# BITalino_V3.net
KiCad netlist of a schematic drawn in EAGLE
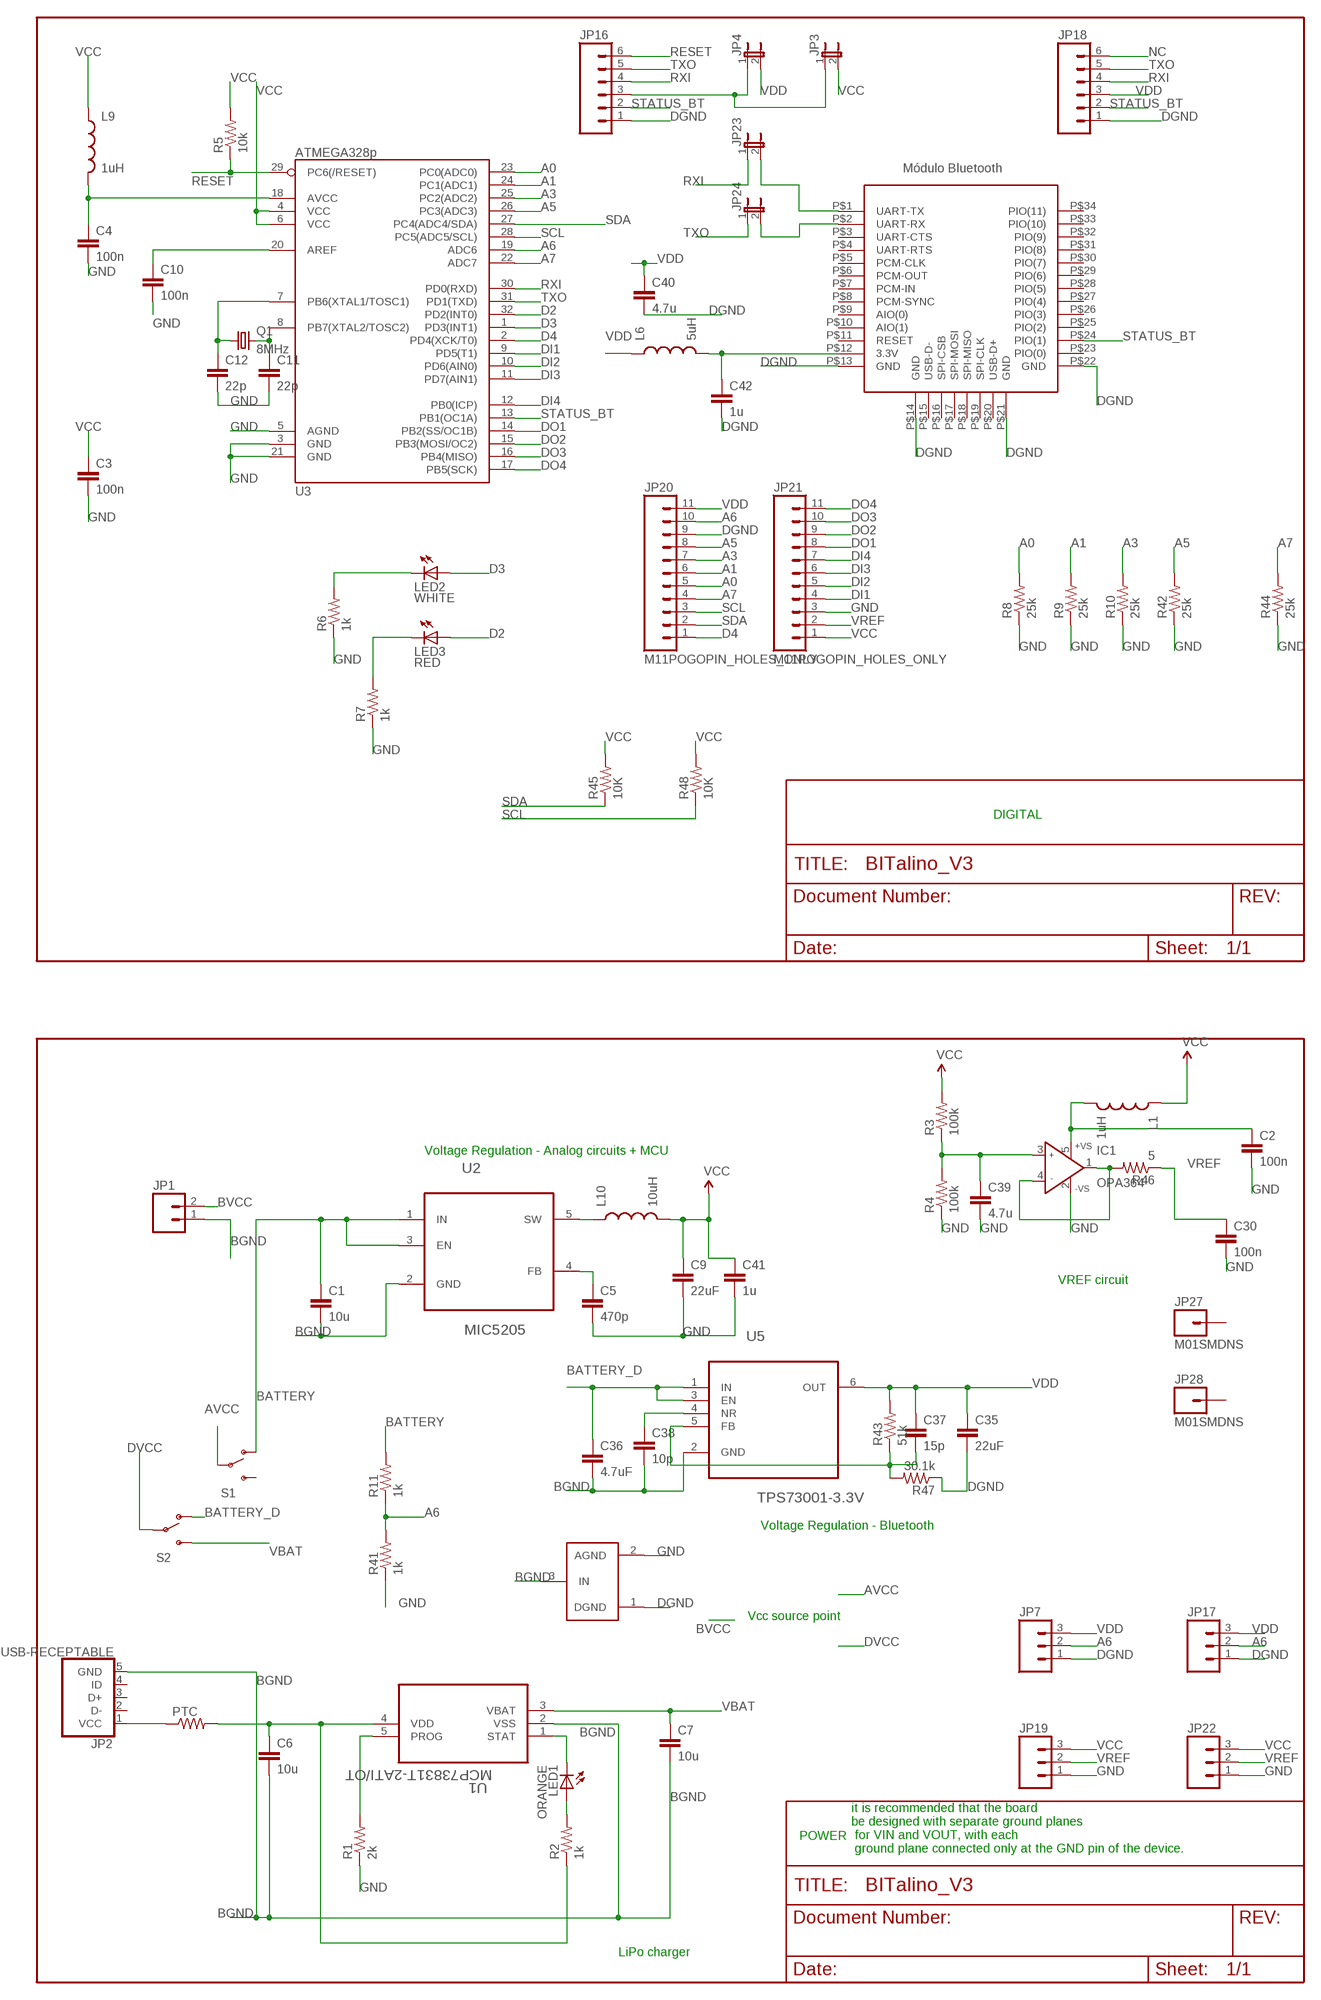
[diagram p0: schematic, sheet 1, part 1 of 3]
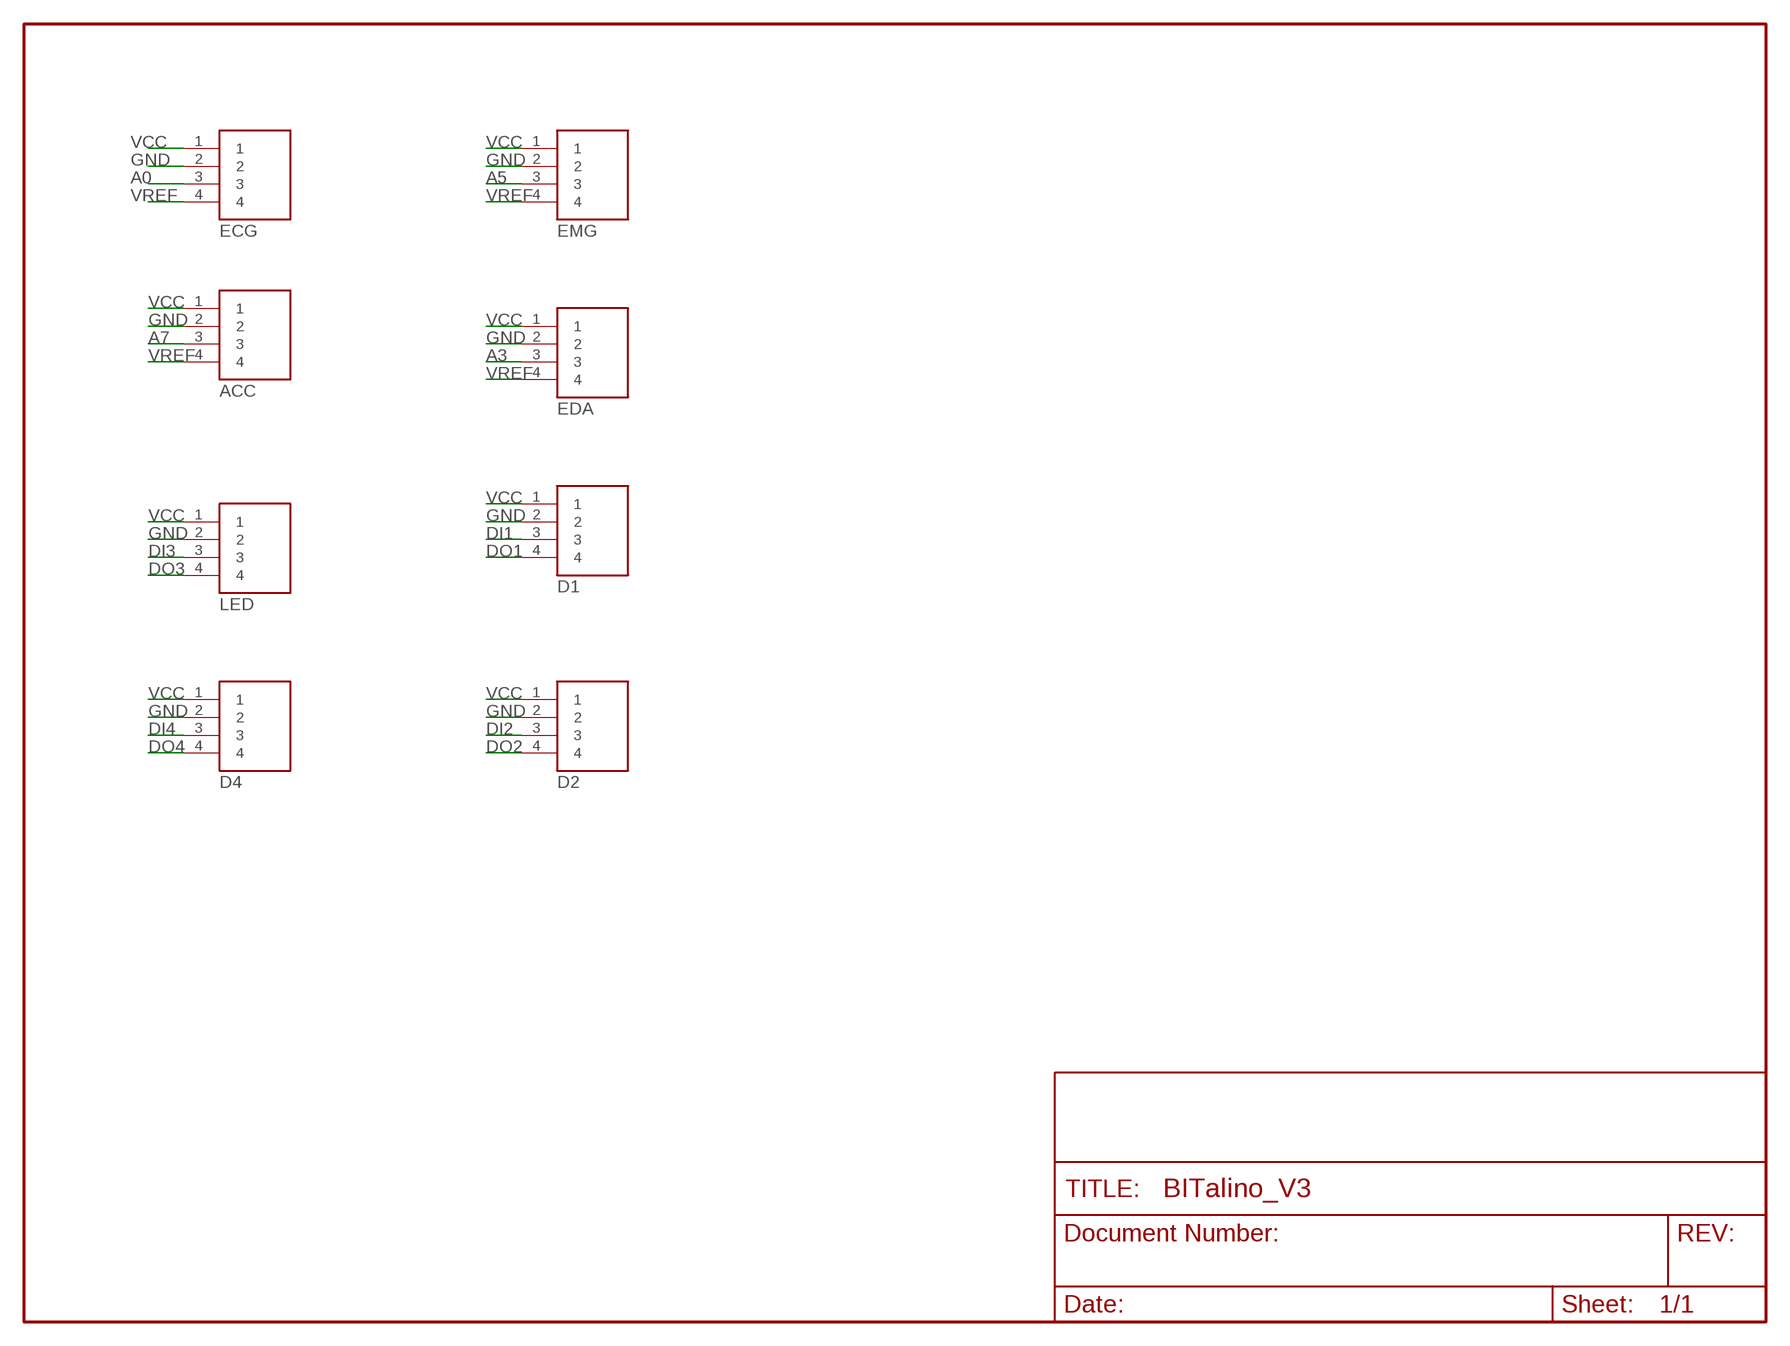
[diagram p1: schematic, sheet 1, part 2 of 3]
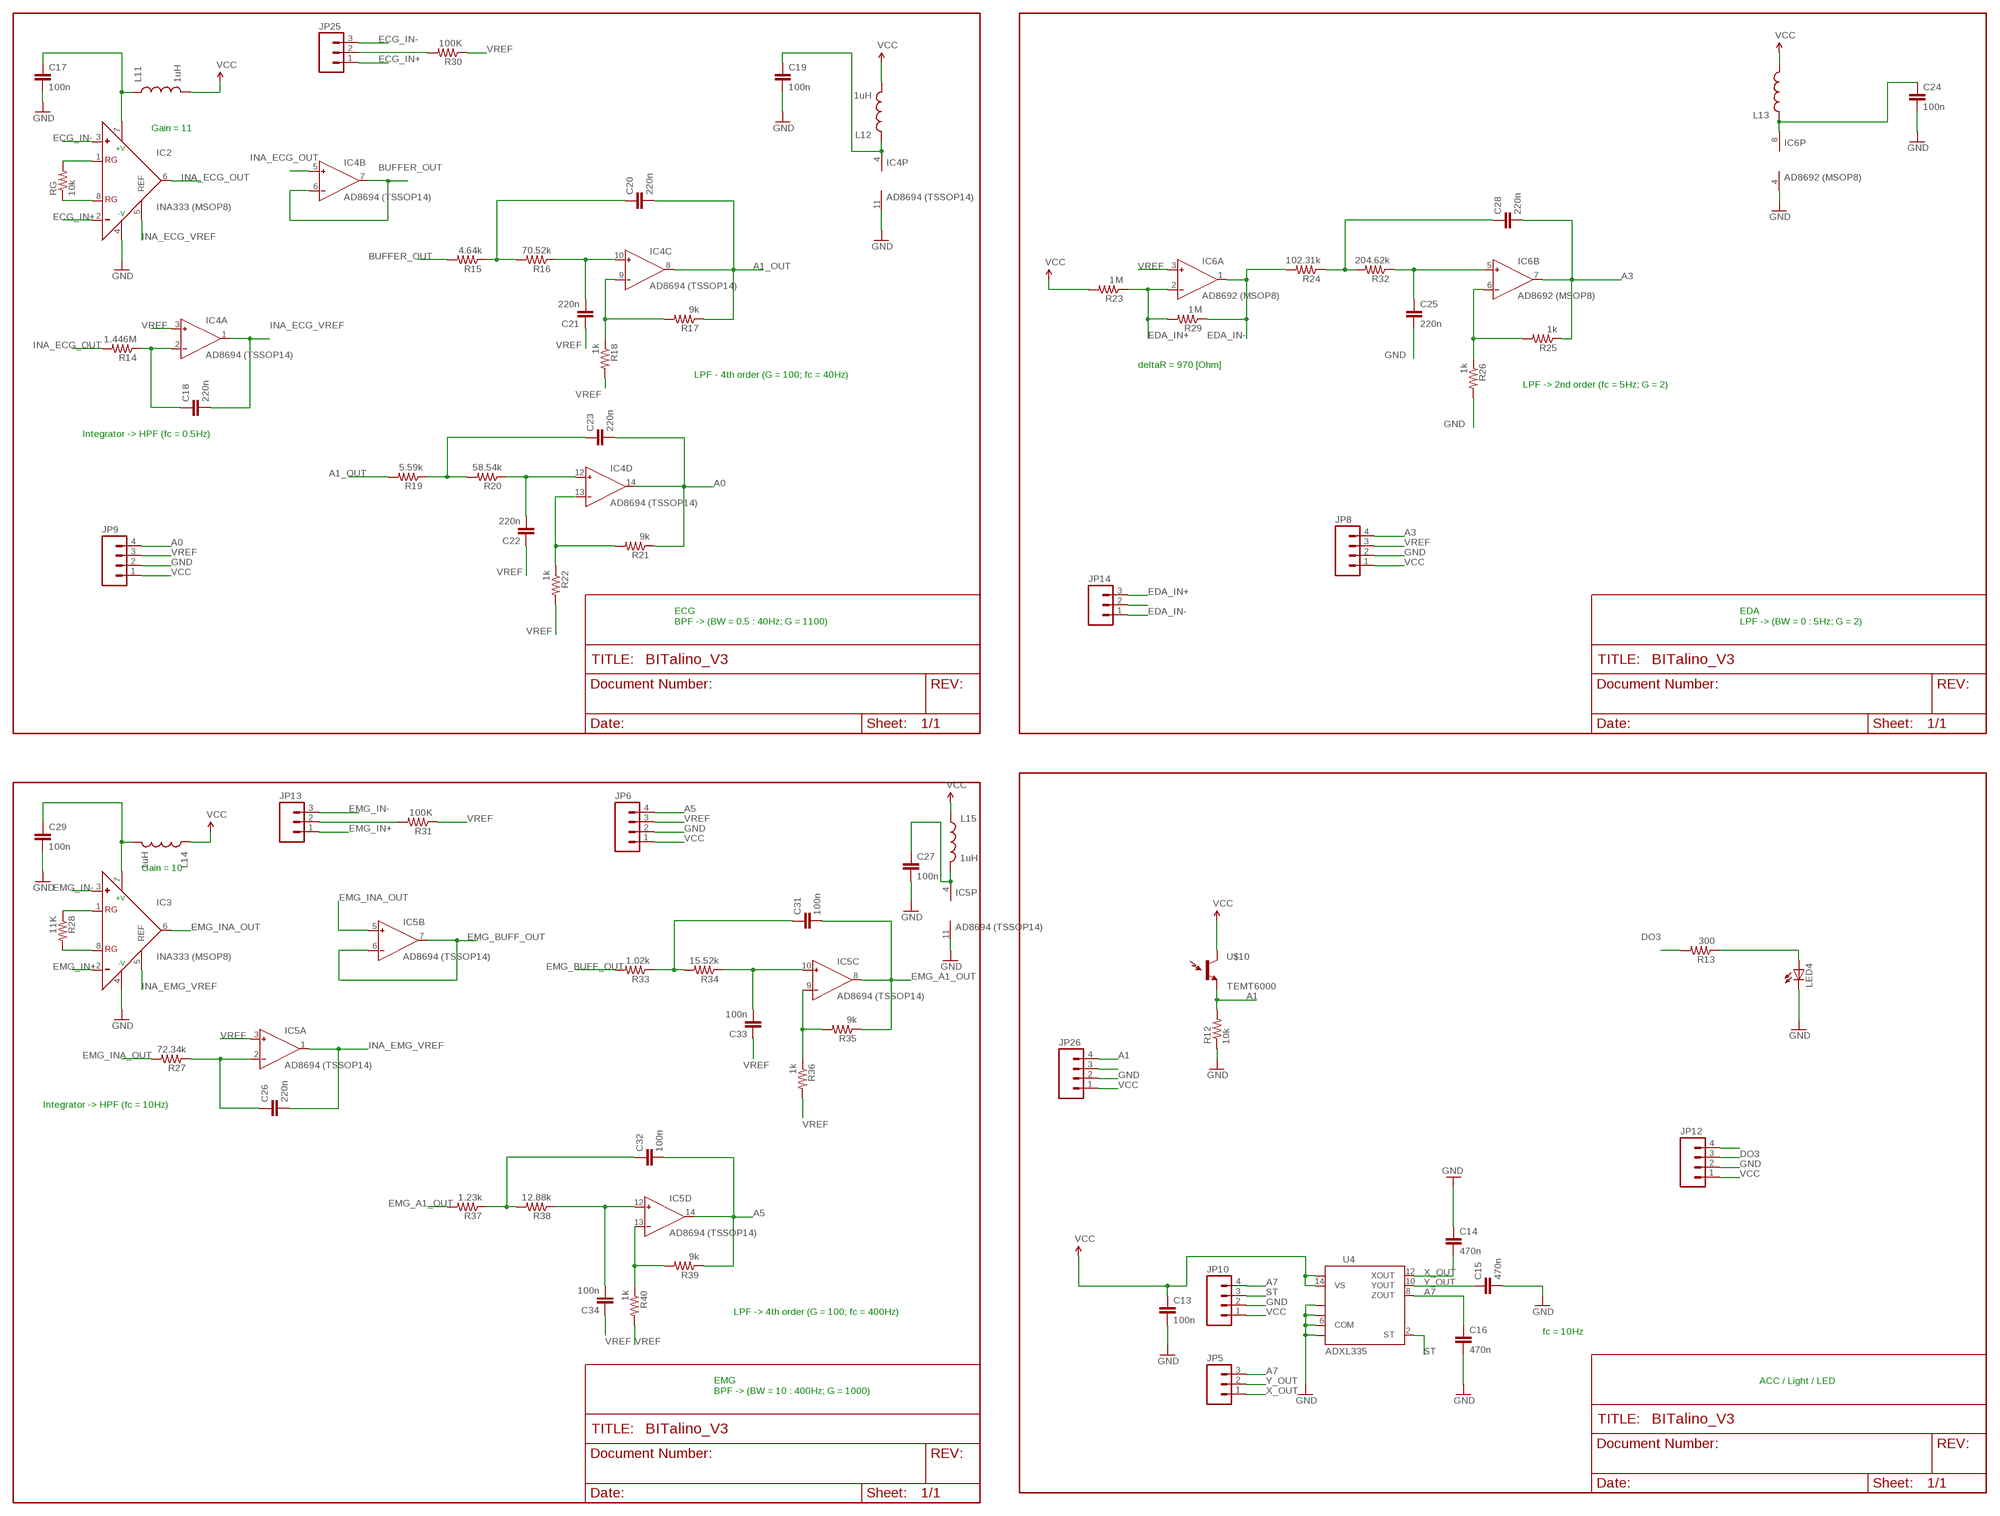
[diagram p2: schematic, sheet 1, part 3 of 3]

(export (version "E")
  (design (tool "Eeschema 10.0.6"))
  (components
    (comp (ref "ACC")
      (value "RJ22")
      (footprint "eagle-import:SMD")
      (libsource (lib "eagle-import") (part "RJ22"))
    )
    (comp (ref "C1")
      (value "10u")
      (footprint "eagle-import:0805")
      (libsource (lib "eagle-import") (part "CAP0805"))
    )
    (comp (ref "C2")
      (value "100n")
      (footprint "eagle-import:0603-CAP")
      (libsource (lib "eagle-import") (part "CAP0603-CAP"))
    )
    (comp (ref "C3")
      (value "100n")
      (footprint "eagle-import:0603-CAP")
      (libsource (lib "eagle-import") (part "CAP0603-CAP"))
    )
    (comp (ref "C4")
      (value "100n")
      (footprint "eagle-import:0603-CAP")
      (libsource (lib "eagle-import") (part "CAP0603-CAP"))
    )
    (comp (ref "C5")
      (value "470p")
      (footprint "eagle-import:0603-CAP")
      (libsource (lib "eagle-import") (part "CAP0603-CAP"))
    )
    (comp (ref "C6")
      (value "10u")
      (footprint "eagle-import:0805")
      (libsource (lib "eagle-import") (part "CAP0805"))
    )
    (comp (ref "C7")
      (value "10u")
      (footprint "eagle-import:0805")
      (libsource (lib "eagle-import") (part "CAP0805"))
    )
    (comp (ref "C9")
      (value "22uF")
      (footprint "eagle-import:0805")
      (libsource (lib "eagle-import") (part "CAP0805"))
    )
    (comp (ref "C10")
      (value "100n")
      (footprint "eagle-import:0603-CAP")
      (libsource (lib "eagle-import") (part "CAP0603-CAP"))
    )
    (comp (ref "C11")
      (value "22p")
      (footprint "eagle-import:0603-CAP")
      (libsource (lib "eagle-import") (part "CAP0603-CAP"))
    )
    (comp (ref "C12")
      (value "22p")
      (footprint "eagle-import:0603-CAP")
      (libsource (lib "eagle-import") (part "CAP0603-CAP"))
    )
    (comp (ref "C13")
      (value "100n")
      (footprint "eagle-import:0603-CAP")
      (libsource (lib "eagle-import") (part "CAP0603-CAP"))
    )
    (comp (ref "C14")
      (value "470n")
      (footprint "eagle-import:0603-CAP")
      (libsource (lib "eagle-import") (part "CAP0603-CAP"))
    )
    (comp (ref "C15")
      (value "470n")
      (footprint "eagle-import:0603-CAP")
      (libsource (lib "eagle-import") (part "CAP0603-CAP"))
    )
    (comp (ref "C16")
      (value "470n")
      (footprint "eagle-import:0603-CAP")
      (libsource (lib "eagle-import") (part "CAP0603-CAP"))
    )
    (comp (ref "C17")
      (value "100n")
      (footprint "eagle-import:0603-CAP")
      (libsource (lib "eagle-import") (part "CAP0603-CAP"))
    )
    (comp (ref "C18")
      (value "220n")
      (footprint "eagle-import:0603-CAP")
      (libsource (lib "eagle-import") (part "CAP0603-CAP"))
    )
    (comp (ref "C19")
      (value "100n")
      (footprint "eagle-import:0603-CAP")
      (libsource (lib "eagle-import") (part "CAP0603-CAP"))
    )
    (comp (ref "C20")
      (value "220n")
      (footprint "eagle-import:0603-CAP")
      (libsource (lib "eagle-import") (part "CAP0603-CAP"))
    )
    (comp (ref "C21")
      (value "220n")
      (footprint "eagle-import:0603-CAP")
      (libsource (lib "eagle-import") (part "CAP0603-CAP"))
    )
    (comp (ref "C22")
      (value "220n")
      (footprint "eagle-import:0603-CAP")
      (libsource (lib "eagle-import") (part "CAP0603-CAP"))
    )
    (comp (ref "C23")
      (value "220n")
      (footprint "eagle-import:0603-CAP")
      (libsource (lib "eagle-import") (part "CAP0603-CAP"))
    )
    (comp (ref "C24")
      (value "100n")
      (footprint "eagle-import:0603-CAP")
      (libsource (lib "eagle-import") (part "CAP0603-CAP"))
    )
    (comp (ref "C25")
      (value "220n")
      (footprint "eagle-import:0603-CAP")
      (libsource (lib "eagle-import") (part "CAP0603-CAP"))
    )
    (comp (ref "C26")
      (value "220n")
      (footprint "eagle-import:0603-CAP")
      (libsource (lib "eagle-import") (part "CAP0603-CAP"))
    )
    (comp (ref "C27")
      (value "100n")
      (footprint "eagle-import:0603-CAP")
      (libsource (lib "eagle-import") (part "CAP0603-CAP"))
    )
    (comp (ref "C28")
      (value "220n")
      (footprint "eagle-import:0603-CAP")
      (libsource (lib "eagle-import") (part "CAP0603-CAP"))
    )
    (comp (ref "C29")
      (value "100n")
      (footprint "eagle-import:0603-CAP")
      (libsource (lib "eagle-import") (part "CAP0603-CAP"))
    )
    (comp (ref "C30")
      (value "100n")
      (footprint "eagle-import:0603-CAP")
      (libsource (lib "eagle-import") (part "CAP0603-CAP"))
    )
    (comp (ref "C31")
      (value "100n")
      (footprint "eagle-import:0603-CAP")
      (libsource (lib "eagle-import") (part "CAP0603-CAP"))
    )
    (comp (ref "C32")
      (value "100n")
      (footprint "eagle-import:0603-CAP")
      (libsource (lib "eagle-import") (part "CAP0603-CAP"))
    )
    (comp (ref "C33")
      (value "100n")
      (footprint "eagle-import:0603-CAP")
      (libsource (lib "eagle-import") (part "CAP0603-CAP"))
    )
    (comp (ref "C34")
      (value "100n")
      (footprint "eagle-import:0603-CAP")
      (libsource (lib "eagle-import") (part "CAP0603-CAP"))
    )
    (comp (ref "C35")
      (value "22uF")
      (footprint "eagle-import:0805")
      (libsource (lib "eagle-import") (part "CAP0805"))
    )
    (comp (ref "C36")
      (value "4.7uF")
      (footprint "eagle-import:0805")
      (libsource (lib "eagle-import") (part "CAP0805"))
    )
    (comp (ref "C37")
      (value "15p")
      (footprint "eagle-import:0603-CAP")
      (libsource (lib "eagle-import") (part "CAP0603-CAP"))
    )
    (comp (ref "C38")
      (value "10p")
      (footprint "eagle-import:0603-CAP")
      (libsource (lib "eagle-import") (part "CAP0603-CAP"))
    )
    (comp (ref "C39")
      (value "4.7u")
      (footprint "eagle-import:0603-CAP")
      (libsource (lib "eagle-import") (part "CAP0603-CAP"))
    )
    (comp (ref "C40")
      (value "4.7u")
      (footprint "eagle-import:0603-CAP")
      (libsource (lib "eagle-import") (part "CAP0603-CAP"))
    )
    (comp (ref "C41")
      (value "1u")
      (footprint "eagle-import:0603-CAP")
      (libsource (lib "eagle-import") (part "CAP0603-CAP"))
    )
    (comp (ref "C42")
      (value "1u")
      (footprint "eagle-import:0603-CAP")
      (libsource (lib "eagle-import") (part "CAP0603-CAP"))
    )
    (comp (ref "D1")
      (value "RJ22")
      (footprint "eagle-import:SMD")
      (libsource (lib "eagle-import") (part "RJ22"))
    )
    (comp (ref "D2")
      (value "RJ22")
      (footprint "eagle-import:SMD")
      (libsource (lib "eagle-import") (part "RJ22"))
    )
    (comp (ref "D4")
      (value "RJ22")
      (footprint "eagle-import:SMD")
      (libsource (lib "eagle-import") (part "RJ22"))
    )
    (comp (ref "ECG")
      (value "RJ22")
      (footprint "eagle-import:SMD")
      (libsource (lib "eagle-import") (part "RJ22"))
    )
    (comp (ref "EDA")
      (value "RJ22")
      (footprint "eagle-import:SMD")
      (libsource (lib "eagle-import") (part "RJ22"))
    )
    (comp (ref "EMG")
      (value "ECG")
      (footprint "eagle-import:SMD")
      (libsource (lib "eagle-import") (part "RJ22"))
    )
    (comp (ref "IC1")
      (value "OPA364")
      (footprint "eagle-import:SOT23-5")
      (fields (field (name "MF") "ALTERA CORPORATION") (field (name "MPN") "AD8541ARTZ-REEL7"))
      (libsource (lib "eagle-import") (part "AD8541RJ"))
    )
    (comp (ref "IC2")
      (value "INA333 (MSOP8)")
      (footprint "eagle-import:MSOP08")
      (fields (field (name "MPN") "AD623ARMZ"))
      (libsource (lib "eagle-import") (part "AD623RM"))
    )
    (comp (ref "IC3")
      (value "INA333 (MSOP8)")
      (footprint "eagle-import:MSOP08")
      (fields (field (name "MPN") "AD623ARMZ"))
      (libsource (lib "eagle-import") (part "AD623RM"))
    )
    (comp (ref "IC4")
      (value "AD8694 (TSSOP14)")
      (footprint "eagle-import:TSSOP14")
      (fields (field (name "MF") "ALTERA CORPORATION") (field (name "MPN") "AD8644ARUZ"))
      (libsource (lib "eagle-import") (part "AD8644RU"))
    )
    (comp (ref "IC5")
      (value "AD8694 (TSSOP14)")
      (footprint "eagle-import:TSSOP14")
      (fields (field (name "MF") "ALTERA CORPORATION") (field (name "MPN") "AD8644ARUZ"))
      (libsource (lib "eagle-import") (part "AD8644RU"))
    )
    (comp (ref "IC6")
      (value "AD8692 (MSOP8)")
      (footprint "eagle-import:MSOP08")
      (fields (field (name "MPN") "AD8656ARMZ"))
      (libsource (lib "eagle-import") (part "AD8656RM"))
    )
    (comp (ref "JP1")
      (value "M02-JST-2-PTH-NO_SILK")
      (footprint "eagle-import:JST-2-PTH-NS")
      (libsource (lib "eagle-import") (part "M02-JST-2-PTH-NO_SILK"))
    )
    (comp (ref "JP2")
      (value "USB-RECEPTABLE")
      (footprint "eagle-import:FCI-10103594-0001LF")
      (libsource (lib "eagle-import") (part "USB-RECEPTABLE"))
    )
    (comp (ref "JP3")
      (value "JUMPER-2SMD-NO-NS")
      (footprint "eagle-import:SJ_2S-NO-NS")
      (libsource (lib "eagle-import") (part "JUMPER-2SMD-NO-NS"))
    )
    (comp (ref "JP4")
      (value "JUMPER-2SMD-NO-NS")
      (footprint "eagle-import:SJ_2S-NO-NS")
      (libsource (lib "eagle-import") (part "JUMPER-2SMD-NO-NS"))
    )
    (comp (ref "JP5")
      (value "M03JST-PTH")
      (footprint "eagle-import:JST-3-PTH")
      (libsource (lib "eagle-import") (part "M03JST-PTH"))
    )
    (comp (ref "JP6")
      (value "M04JST-PTH")
      (footprint "eagle-import:JST-4-PTH")
      (libsource (lib "eagle-import") (part "M04JST-PTH"))
    )
    (comp (ref "JP7")
      (value "M031X03_NO_SILK")
      (footprint "eagle-import:1X03_NO_SILK")
      (libsource (lib "eagle-import") (part "M031X03_NO_SILK"))
    )
    (comp (ref "JP8")
      (value "M04JST-PTH")
      (footprint "eagle-import:JST-4-PTH")
      (libsource (lib "eagle-import") (part "M04JST-PTH"))
    )
    (comp (ref "JP9")
      (value "M04JST-PTH")
      (footprint "eagle-import:JST-4-PTH")
      (libsource (lib "eagle-import") (part "M04JST-PTH"))
    )
    (comp (ref "JP10")
      (value "M04JST-PTH")
      (footprint "eagle-import:JST-4-PTH")
      (libsource (lib "eagle-import") (part "M04JST-PTH"))
    )
    (comp (ref "JP12")
      (value "M04JST-PTH")
      (footprint "eagle-import:JST-4-PTH")
      (libsource (lib "eagle-import") (part "M04JST-PTH"))
    )
    (comp (ref "JP13")
      (value "M03JST-PTH")
      (footprint "eagle-import:JST-3-PTH")
      (libsource (lib "eagle-import") (part "M03JST-PTH"))
    )
    (comp (ref "JP14")
      (value "M03JST-PTH")
      (footprint "eagle-import:JST-3-PTH")
      (libsource (lib "eagle-import") (part "M03JST-PTH"))
    )
    (comp (ref "JP16")
      (value "M06POGOPIN_HOLES_ONLY")
      (footprint "eagle-import:1X06_HOLES_ONLY")
      (libsource (lib "eagle-import") (part "M06POGOPIN_HOLES_ONLY"))
    )
    (comp (ref "JP17")
      (value "M031X03_NO_SILK")
      (footprint "eagle-import:1X03_NO_SILK")
      (libsource (lib "eagle-import") (part "M031X03_NO_SILK"))
    )
    (comp (ref "JP18")
      (value "M06POGOPIN_HOLES_ONLY")
      (footprint "eagle-import:1X06_HOLES_ONLY")
      (libsource (lib "eagle-import") (part "M06POGOPIN_HOLES_ONLY"))
    )
    (comp (ref "JP19")
      (value "M031X03_NO_SILK")
      (footprint "eagle-import:1X03_NO_SILK")
      (libsource (lib "eagle-import") (part "M031X03_NO_SILK"))
    )
    (comp (ref "JP20")
      (value "M11POGOPIN_HOLES_ONLY")
      (footprint "eagle-import:1X11_HOLES_ONLY")
      (libsource (lib "eagle-import") (part "M11POGOPIN_HOLES_ONLY"))
    )
    (comp (ref "JP21")
      (value "M11POGOPIN_HOLES_ONLY")
      (footprint "eagle-import:1X11_HOLES_ONLY")
      (libsource (lib "eagle-import") (part "M11POGOPIN_HOLES_ONLY"))
    )
    (comp (ref "JP22")
      (value "M031X03_NO_SILK")
      (footprint "eagle-import:1X03_NO_SILK")
      (libsource (lib "eagle-import") (part "M031X03_NO_SILK"))
    )
    (comp (ref "JP23")
      (value "JUMPER-2SMD-NO-NS")
      (footprint "eagle-import:SJ_2S-NO-NS")
      (libsource (lib "eagle-import") (part "JUMPER-2SMD-NO-NS"))
    )
    (comp (ref "JP24")
      (value "JUMPER-2SMD-NO-NS")
      (footprint "eagle-import:SJ_2S-NO-NS")
      (libsource (lib "eagle-import") (part "JUMPER-2SMD-NO-NS"))
    )
    (comp (ref "JP25")
      (value "M03JST-PTH")
      (footprint "eagle-import:JST-3-PTH")
      (libsource (lib "eagle-import") (part "M03JST-PTH"))
    )
    (comp (ref "JP26")
      (value "M04JST-PTH")
      (footprint "eagle-import:JST-4-PTH")
      (libsource (lib "eagle-import") (part "M04JST-PTH"))
    )
    (comp (ref "JP27")
      (value "M01SMDNS")
      (footprint "eagle-import:1X01NS")
      (libsource (lib "eagle-import") (part "M01SMDNS"))
    )
    (comp (ref "JP28")
      (value "M01SMDNS")
      (footprint "eagle-import:1X01NS")
      (libsource (lib "eagle-import") (part "M01SMDNS"))
    )
    (comp (ref "L1")
      (value "1uH")
      (footprint "eagle-import:0603")
      (libsource (lib "eagle-import") (part "INDUCTOR0603"))
    )
    (comp (ref "L6")
      (value "5uH")
      (footprint "eagle-import:0805")
      (libsource (lib "eagle-import") (part "INDUCTOR0805"))
    )
    (comp (ref "L9")
      (value "1uH")
      (footprint "eagle-import:0603")
      (libsource (lib "eagle-import") (part "INDUCTOR0603"))
    )
    (comp (ref "L10")
      (value "10uH")
      (footprint "eagle-import:0805")
      (libsource (lib "eagle-import") (part "INDUCTOR0805"))
    )
    (comp (ref "L11")
      (value "1uH")
      (footprint "eagle-import:0603")
      (libsource (lib "eagle-import") (part "INDUCTOR0603"))
    )
    (comp (ref "L12")
      (value "1uH")
      (footprint "eagle-import:0603")
      (libsource (lib "eagle-import") (part "INDUCTOR0603"))
    )
    (comp (ref "L13")
      (value "INDUCTOR0603")
      (footprint "eagle-import:0603")
      (libsource (lib "eagle-import") (part "INDUCTOR0603"))
    )
    (comp (ref "L14")
      (value "1uH")
      (footprint "eagle-import:0603")
      (libsource (lib "eagle-import") (part "INDUCTOR0603"))
    )
    (comp (ref "L15")
      (value "1uH")
      (footprint "eagle-import:0603")
      (libsource (lib "eagle-import") (part "INDUCTOR0603"))
    )
    (comp (ref "LED")
      (value "RJ22")
      (footprint "eagle-import:SMD")
      (libsource (lib "eagle-import") (part "RJ22"))
    )
    (comp (ref "LED1")
      (value "ORANGE")
      (footprint "eagle-import:LED-0603")
      (libsource (lib "eagle-import") (part "LED0603"))
    )
    (comp (ref "LED2")
      (value "WHITE")
      (footprint "eagle-import:LED-0603")
      (libsource (lib "eagle-import") (part "LED0603"))
    )
    (comp (ref "LED3")
      (value "RED")
      (footprint "eagle-import:LED-0603")
      (libsource (lib "eagle-import") (part "LED0603"))
    )
    (comp (ref "LED4")
      (value "LED1206")
      (footprint "eagle-import:LED-1206")
      (libsource (lib "eagle-import") (part "LED1206"))
    )
    (comp (ref "PTC")
      (value "RESISTOR0805-RES")
      (footprint "eagle-import:0805")
      (libsource (lib "eagle-import") (part "RESISTOR0805-RES"))
    )
    (comp (ref "Q1")
      (value "8MHz")
      (footprint "eagle-import:CTS406")
      (libsource (lib "eagle-import") (part "CRYSTALCTS406"))
    )
    (comp (ref "R1")
      (value "2k")
      (footprint "eagle-import:0603-RES")
      (libsource (lib "eagle-import") (part "RESISTOR0603-RES"))
    )
    (comp (ref "R2")
      (value "1k")
      (footprint "eagle-import:0603-RES")
      (libsource (lib "eagle-import") (part "RESISTOR0603-RES"))
    )
    (comp (ref "R3")
      (value "100k")
      (footprint "eagle-import:0603-RES")
      (libsource (lib "eagle-import") (part "RESISTOR0603-RES"))
    )
    (comp (ref "R4")
      (value "100k")
      (footprint "eagle-import:0603-RES")
      (libsource (lib "eagle-import") (part "RESISTOR0603-RES"))
    )
    (comp (ref "R5")
      (value "10k")
      (footprint "eagle-import:0603-RES")
      (libsource (lib "eagle-import") (part "RESISTOR0603-RES"))
    )
    (comp (ref "R6")
      (value "1k")
      (footprint "eagle-import:0603-RES")
      (libsource (lib "eagle-import") (part "RESISTOR0603-RES"))
    )
    (comp (ref "R7")
      (value "1k")
      (footprint "eagle-import:0603-RES")
      (libsource (lib "eagle-import") (part "RESISTOR0603-RES"))
    )
    (comp (ref "R8")
      (value "25k")
      (footprint "eagle-import:0603-RES")
      (libsource (lib "eagle-import") (part "RESISTOR0603-RES"))
    )
    (comp (ref "R9")
      (value "25k")
      (footprint "eagle-import:0603-RES")
      (libsource (lib "eagle-import") (part "RESISTOR0603-RES"))
    )
    (comp (ref "R10")
      (value "25k")
      (footprint "eagle-import:0603-RES")
      (libsource (lib "eagle-import") (part "RESISTOR0603-RES"))
    )
    (comp (ref "R11")
      (value "1k")
      (footprint "eagle-import:0603-RES")
      (libsource (lib "eagle-import") (part "RESISTOR0603-RES"))
    )
    (comp (ref "R12")
      (value "10k")
      (footprint "eagle-import:0603-RES")
      (libsource (lib "eagle-import") (part "RESISTOR0603-RES"))
    )
    (comp (ref "R13")
      (value "300")
      (footprint "eagle-import:0603-RES")
      (libsource (lib "eagle-import") (part "RESISTOR0603-RES"))
    )
    (comp (ref "R14")
      (value "1.446M")
      (footprint "eagle-import:0603-RES")
      (libsource (lib "eagle-import") (part "RESISTOR0603-RES"))
    )
    (comp (ref "R15")
      (value "4.64k")
      (footprint "eagle-import:0603-RES")
      (libsource (lib "eagle-import") (part "RESISTOR0603-RES"))
    )
    (comp (ref "R16")
      (value "70.52k")
      (footprint "eagle-import:0603-RES")
      (libsource (lib "eagle-import") (part "RESISTOR0603-RES"))
    )
    (comp (ref "R17")
      (value "9k")
      (footprint "eagle-import:0603-RES")
      (libsource (lib "eagle-import") (part "RESISTOR0603-RES"))
    )
    (comp (ref "R18")
      (value "1k")
      (footprint "eagle-import:0603-RES")
      (libsource (lib "eagle-import") (part "RESISTOR0603-RES"))
    )
    (comp (ref "R19")
      (value "5.59k")
      (footprint "eagle-import:0603-RES")
      (libsource (lib "eagle-import") (part "RESISTOR0603-RES"))
    )
    (comp (ref "R20")
      (value "58.54k")
      (footprint "eagle-import:0603-RES")
      (libsource (lib "eagle-import") (part "RESISTOR0603-RES"))
    )
    (comp (ref "R21")
      (value "9k")
      (footprint "eagle-import:0603-RES")
      (libsource (lib "eagle-import") (part "RESISTOR0603-RES"))
    )
    (comp (ref "R22")
      (value "1k")
      (footprint "eagle-import:0603-RES")
      (libsource (lib "eagle-import") (part "RESISTOR0603-RES"))
    )
    (comp (ref "R23")
      (value "1M")
      (footprint "eagle-import:0603-RES")
      (libsource (lib "eagle-import") (part "RESISTOR0603-RES"))
    )
    (comp (ref "R24")
      (value "102.31k")
      (footprint "eagle-import:0603-RES")
      (libsource (lib "eagle-import") (part "RESISTOR0603-RES"))
    )
    (comp (ref "R25")
      (value "1k")
      (footprint "eagle-import:0603-RES")
      (libsource (lib "eagle-import") (part "RESISTOR0603-RES"))
    )
    (comp (ref "R26")
      (value "1k")
      (footprint "eagle-import:0603-RES")
      (libsource (lib "eagle-import") (part "RESISTOR0603-RES"))
    )
    (comp (ref "R27")
      (value "72.34k")
      (footprint "eagle-import:0603-RES")
      (libsource (lib "eagle-import") (part "RESISTOR0603-RES"))
    )
    (comp (ref "R28")
      (value "11K")
      (footprint "eagle-import:0603-RES")
      (libsource (lib "eagle-import") (part "RESISTOR0603-RES"))
    )
    (comp (ref "R29")
      (value "1M")
      (footprint "eagle-import:0603-RES")
      (libsource (lib "eagle-import") (part "RESISTOR0603-RES"))
    )
    (comp (ref "R30")
      (value "100K")
      (footprint "eagle-import:0603-RES")
      (libsource (lib "eagle-import") (part "RESISTOR0603-RES"))
    )
    (comp (ref "R31")
      (value "100K")
      (footprint "eagle-import:0603-RES")
      (libsource (lib "eagle-import") (part "RESISTOR0603-RES"))
    )
    (comp (ref "R32")
      (value "204.62k")
      (footprint "eagle-import:0603-RES")
      (libsource (lib "eagle-import") (part "RESISTOR0603-RES"))
    )
    (comp (ref "R33")
      (value "1.02k")
      (footprint "eagle-import:0603-RES")
      (libsource (lib "eagle-import") (part "RESISTOR0603-RES"))
    )
    (comp (ref "R34")
      (value "15.52k")
      (footprint "eagle-import:0603-RES")
      (libsource (lib "eagle-import") (part "RESISTOR0603-RES"))
    )
    (comp (ref "R35")
      (value "9k")
      (footprint "eagle-import:0603-RES")
      (libsource (lib "eagle-import") (part "RESISTOR0603-RES"))
    )
    (comp (ref "R36")
      (value "1k")
      (footprint "eagle-import:0603-RES")
      (libsource (lib "eagle-import") (part "RESISTOR0603-RES"))
    )
    (comp (ref "R37")
      (value "1.23k")
      (footprint "eagle-import:0603-RES")
      (libsource (lib "eagle-import") (part "RESISTOR0603-RES"))
    )
    (comp (ref "R38")
      (value "12.88k")
      (footprint "eagle-import:0603-RES")
      (libsource (lib "eagle-import") (part "RESISTOR0603-RES"))
    )
    (comp (ref "R39")
      (value "9k")
      (footprint "eagle-import:0603-RES")
      (libsource (lib "eagle-import") (part "RESISTOR0603-RES"))
    )
    (comp (ref "R40")
      (value "1k")
      (footprint "eagle-import:0603-RES")
      (libsource (lib "eagle-import") (part "RESISTOR0603-RES"))
    )
    (comp (ref "R41")
      (value "1k")
      (footprint "eagle-import:0603-RES")
      (libsource (lib "eagle-import") (part "RESISTOR0603-RES"))
    )
    (comp (ref "R42")
      (value "25k")
      (footprint "eagle-import:0603-RES")
      (libsource (lib "eagle-import") (part "RESISTOR0603-RES"))
    )
    (comp (ref "R43")
      (value "51k")
      (footprint "eagle-import:0603-RES")
      (libsource (lib "eagle-import") (part "RESISTOR0603-RES"))
    )
    (comp (ref "R44")
      (value "25k")
      (footprint "eagle-import:0603-RES")
      (libsource (lib "eagle-import") (part "RESISTOR0603-RES"))
    )
    (comp (ref "R45")
      (value "10K")
      (footprint "eagle-import:0603-RES")
      (libsource (lib "eagle-import") (part "RESISTOR0603-RES"))
    )
    (comp (ref "R46")
      (value "5")
      (footprint "eagle-import:0603-RES")
      (libsource (lib "eagle-import") (part "RESISTOR0603-RES"))
    )
    (comp (ref "R47")
      (value "30.1k")
      (footprint "eagle-import:0603-RES")
      (libsource (lib "eagle-import") (part "RESISTOR0603-RES"))
    )
    (comp (ref "R48")
      (value "10K")
      (footprint "eagle-import:0603-RES")
      (libsource (lib "eagle-import") (part "RESISTOR0603-RES"))
    )
    (comp (ref "RG")
      (value "10k")
      (footprint "eagle-import:0603-RES")
      (libsource (lib "eagle-import") (part "RESISTOR0603-RES"))
    )
    (comp (ref "S1")
      (value "SWITCH-SPSTPTH")
      (footprint "eagle-import:SWITCH-SPDT")
      (libsource (lib "eagle-import") (part "SWITCH-SPSTPTH"))
    )
    (comp (ref "S2")
      (value "SWITCH-SPSTPTH")
      (footprint "eagle-import:SWITCH-SPDT")
      (libsource (lib "eagle-import") (part "SWITCH-SPSTPTH"))
    )
    (comp (ref "U$1")
      (value "BLUETOOTH")
      (footprint "eagle-import:BLUETOOTH")
      (libsource (lib "eagle-import") (part "BLUETOOTH"))
    )
    (comp (ref "U$2")
      (value "GND_CONNECT")
      (footprint "eagle-import:GND_CONNECT")
      (libsource (lib "eagle-import") (part "GND_CONNECT"))
    )
    (comp (ref "U$10")
      (value "TEMT6000")
      (footprint "eagle-import:TEMT6000-SEN")
      (libsource (lib "eagle-import") (part "TEMT6000"))
    )
    (comp (ref "U1")
      (value "MCP73831T-2ATI/OT")
      (footprint "eagle-import:SOT95P300X145-5N")
      (libsource (lib "eagle-import") (part "MCP73831T-2ATI/OT"))
    )
    (comp (ref "U2")
      (value "MIC5205")
      (footprint "eagle-import:SOT95P280X130-5N")
      (fields
        (field (name "MPN") "ADP2108AUJZ-3.3-R7")
        (field (name "MPN_1") "ADP2108AUJZ-3.3-R7")
        (field (name "OC_FARNELL") "2112606")
        (field (name "PACKAGE") "TSOT")
        (field (name "SUPPLIER") "ANALOG DEVICES")
      )
      (libsource (lib "eagle-import") (part "ADP2108AUJZ-3.3-R7"))
    )
    (comp (ref "U3")
      (value "ATMEGA328p")
      (footprint "eagle-import:TQFP32-08")
      (libsource (lib "eagle-import") (part "ATMEGA168"))
    )
    (comp (ref "U4")
      (value "ADXL335")
      (footprint "eagle-import:LFCSP-16")
      (libsource (lib "eagle-import") (part "ADXL335"))
    )
    (comp (ref "U5")
      (value "TPS73001-3.3V")
      (footprint "eagle-import:SOT95P280X145-6N")
      (fields (field (name "MPN") "TPS73001DBVT"))
      (libsource (lib "eagle-import") (part "TPS73001DBVT"))
    )
  )
  (nets
    (net (code "1") (name "/A0") (class "Default")
      (node (ref "C23") (pin "2") (pinfunction "2_2") (pintype "passive"))
      (node (ref "ECG") (pin "3") (pinfunction "3_3") (pintype "bidirectional"))
      (node (ref "IC4") (pin "14") (pinfunction "OUT_14") (pintype "output"))
      (node (ref "JP20") (pin "5") (pinfunction "5_5") (pintype "passive"))
      (node (ref "JP9") (pin "4") (pinfunction "4_4") (pintype "passive"))
      (node (ref "R21") (pin "1") (pinfunction "1_1") (pintype "passive"))
      (node (ref "R8") (pin "2") (pinfunction "2_2") (pintype "passive"))
      (node (ref "U3") (pin "23") (pinfunction "PC0(ADC0)_23") (pintype "bidirectional"))
    )
    (net (code "2") (name "/A1") (class "Default")
      (node (ref "JP20") (pin "6") (pinfunction "6_6") (pintype "passive"))
      (node (ref "JP26") (pin "4") (pinfunction "4_4") (pintype "passive"))
      (node (ref "R12") (pin "2") (pinfunction "2_2") (pintype "passive"))
      (node (ref "R9") (pin "2") (pinfunction "2_2") (pintype "passive"))
      (node (ref "U$10") (pin "EMITTER") (pinfunction "E1_EMITTER") (pintype "passive"))
      (node (ref "U3") (pin "24") (pinfunction "PC1(ADC1)_24") (pintype "bidirectional"))
    )
    (net (code "3") (name "/A1_OUT") (class "Default")
      (node (ref "C20") (pin "2") (pinfunction "2_2") (pintype "passive"))
      (node (ref "IC4") (pin "8") (pinfunction "OUT_8") (pintype "output"))
      (node (ref "R17") (pin "1") (pinfunction "1_1") (pintype "passive"))
      (node (ref "R19") (pin "2") (pinfunction "2_2") (pintype "passive"))
    )
    (net (code "4") (name "/A3") (class "Default")
      (node (ref "C28") (pin "2") (pinfunction "2_2") (pintype "passive"))
      (node (ref "EDA") (pin "3") (pinfunction "3_3") (pintype "bidirectional"))
      (node (ref "IC6") (pin "7") (pinfunction "OUT_7") (pintype "output"))
      (node (ref "JP20") (pin "7") (pinfunction "7_7") (pintype "passive"))
      (node (ref "JP8") (pin "4") (pinfunction "4_4") (pintype "passive"))
      (node (ref "R10") (pin "2") (pinfunction "2_2") (pintype "passive"))
      (node (ref "R25") (pin "1") (pinfunction "1_1") (pintype "passive"))
      (node (ref "U3") (pin "25") (pinfunction "PC2(ADC2)_25") (pintype "bidirectional"))
    )
    (net (code "5") (name "/A5") (class "Default")
      (node (ref "C32") (pin "2") (pinfunction "2_2") (pintype "passive"))
      (node (ref "EMG") (pin "3") (pinfunction "3_3") (pintype "bidirectional"))
      (node (ref "IC5") (pin "14") (pinfunction "OUT_14") (pintype "output"))
      (node (ref "JP20") (pin "8") (pinfunction "8_8") (pintype "passive"))
      (node (ref "JP6") (pin "4") (pinfunction "4_4") (pintype "passive"))
      (node (ref "R39") (pin "1") (pinfunction "1_1") (pintype "passive"))
      (node (ref "R42") (pin "2") (pinfunction "2_2") (pintype "passive"))
      (node (ref "U3") (pin "26") (pinfunction "PC3(ADC3)_26") (pintype "bidirectional"))
    )
    (net (code "6") (name "/A6") (class "Default")
      (node (ref "JP17") (pin "2") (pinfunction "2_2") (pintype "passive"))
      (node (ref "JP20") (pin "10") (pinfunction "10_10") (pintype "passive"))
      (node (ref "JP7") (pin "2") (pinfunction "2_2") (pintype "passive"))
      (node (ref "R11") (pin "1") (pinfunction "1_1") (pintype "passive"))
      (node (ref "R41") (pin "2") (pinfunction "2_2") (pintype "passive"))
      (node (ref "U3") (pin "19") (pinfunction "ADC6_19") (pintype "bidirectional"))
    )
    (net (code "7") (name "/A7") (class "Default")
      (node (ref "ACC") (pin "3") (pinfunction "3_3") (pintype "bidirectional"))
      (node (ref "C16") (pin "1") (pinfunction "1_1") (pintype "passive"))
      (node (ref "JP10") (pin "4") (pinfunction "4_4") (pintype "passive"))
      (node (ref "JP20") (pin "4") (pinfunction "4_4") (pintype "passive"))
      (node (ref "JP5") (pin "3") (pinfunction "3_3") (pintype "passive"))
      (node (ref "R44") (pin "2") (pinfunction "2_2") (pintype "passive"))
      (node (ref "U3") (pin "22") (pinfunction "ADC7_22") (pintype "bidirectional"))
      (node (ref "U4") (pin "8") (pinfunction "ZOUT_8") (pintype "bidirectional"))
    )
    (net (code "8") (name "/AVCC") (class "Default")
      (node (ref "S1") (pin "2") (pinfunction "P_2") (pintype "passive"))
    )
    (net (code "9") (name "/BATTERY") (class "Default")
      (node (ref "C1") (pin "1") (pinfunction "1_1") (pintype "passive"))
      (node (ref "R11") (pin "2") (pinfunction "2_2") (pintype "passive"))
      (node (ref "S1") (pin "1") (pinfunction "O_1") (pintype "passive"))
      (node (ref "U2") (pin "1") (pinfunction "IN_1") (pintype "input"))
      (node (ref "U2") (pin "3") (pinfunction "EN_3") (pintype "input"))
    )
    (net (code "10") (name "/BATTERY_D") (class "Default")
      (node (ref "C36") (pin "1") (pinfunction "1_1") (pintype "passive"))
      (node (ref "S2") (pin "1") (pinfunction "O_1") (pintype "passive"))
      (node (ref "U5") (pin "1") (pinfunction "IN_1") (pintype "input"))
      (node (ref "U5") (pin "3") (pinfunction "EN_3") (pintype "input"))
    )
    (net (code "11") (name "/BGND") (class "Default")
      (node (ref "C1") (pin "2") (pinfunction "2_2") (pintype "passive"))
      (node (ref "C36") (pin "2") (pinfunction "2_2") (pintype "passive"))
      (node (ref "C38") (pin "2") (pinfunction "2_2") (pintype "passive"))
      (node (ref "C6") (pin "2") (pinfunction "2_2") (pintype "passive"))
      (node (ref "C7") (pin "2") (pinfunction "2_2") (pintype "passive"))
      (node (ref "JP1") (pin "1") (pinfunction "1_1") (pintype "passive"))
      (node (ref "JP2") (pin "5") (pinfunction "GND_5") (pintype "bidirectional"))
      (node (ref "U$2") (pin "3") (pinfunction "IN_3") (pintype "bidirectional"))
      (node (ref "U1") (pin "2") (pinfunction "VSS_2") (pintype "passive"))
      (node (ref "U2") (pin "2") (pinfunction "GND_2") (pintype "passive"))
      (node (ref "U5") (pin "2") (pinfunction "GND_2") (pintype "passive"))
    )
    (net (code "12") (name "/BUFFER_OUT") (class "Default")
      (node (ref "IC4") (pin "6") (pinfunction "IN-_6") (pintype "input"))
      (node (ref "IC4") (pin "7") (pinfunction "OUT_7") (pintype "output"))
      (node (ref "R15") (pin "2") (pinfunction "2_2") (pintype "passive"))
    )
    (net (code "13") (name "/BVCC") (class "Default")
      (node (ref "JP1") (pin "2") (pinfunction "2_2") (pintype "passive"))
    )
    (net (code "14") (name "/D2") (class "Default")
      (node (ref "LED3") (pin "A") (pinfunction "A_A") (pintype "passive"))
      (node (ref "U3") (pin "32") (pinfunction "PD2(INT0)_32") (pintype "bidirectional"))
    )
    (net (code "15") (name "/D3") (class "Default")
      (node (ref "LED2") (pin "A") (pinfunction "A_A") (pintype "passive"))
      (node (ref "U3") (pin "1") (pinfunction "PD3(INT1)_1") (pintype "bidirectional"))
    )
    (net (code "16") (name "/D4") (class "Default")
      (node (ref "JP20") (pin "1") (pinfunction "1_1") (pintype "passive"))
      (node (ref "U3") (pin "2") (pinfunction "PD4(XCK/T0)_2") (pintype "bidirectional"))
    )
    (net (code "17") (name "/DGND") (class "Default")
      (node (ref "C35") (pin "2") (pinfunction "2_2") (pintype "passive"))
      (node (ref "C40") (pin "2") (pinfunction "2_2") (pintype "passive"))
      (node (ref "C42") (pin "2") (pinfunction "2_2") (pintype "passive"))
      (node (ref "JP16") (pin "1") (pinfunction "1_1") (pintype "passive"))
      (node (ref "JP17") (pin "1") (pinfunction "1_1") (pintype "passive"))
      (node (ref "JP18") (pin "1") (pinfunction "1_1") (pintype "passive"))
      (node (ref "JP20") (pin "9") (pinfunction "9_9") (pintype "passive"))
      (node (ref "JP7") (pin "1") (pinfunction "1_1") (pintype "passive"))
      (node (ref "R47") (pin "1") (pinfunction "1_1") (pintype "passive"))
      (node (ref "U$1") (pin "P$13") (pinfunction "GND_P$13") (pintype "bidirectional"))
      (node (ref "U$1") (pin "P$14") (pinfunction "GND_P$14") (pintype "bidirectional"))
      (node (ref "U$1") (pin "P$21") (pinfunction "GND_P$21") (pintype "bidirectional"))
      (node (ref "U$1") (pin "P$22") (pinfunction "GND_P$22") (pintype "bidirectional"))
      (node (ref "U$2") (pin "1") (pinfunction "DGND_1") (pintype "bidirectional"))
    )
    (net (code "18") (name "/DI1") (class "Default")
      (node (ref "D1") (pin "3") (pinfunction "3_3") (pintype "bidirectional"))
      (node (ref "JP21") (pin "4") (pinfunction "4_4") (pintype "passive"))
      (node (ref "U3") (pin "9") (pinfunction "PD5(T1)_9") (pintype "bidirectional"))
    )
    (net (code "19") (name "/DI2") (class "Default")
      (node (ref "D2") (pin "3") (pinfunction "3_3") (pintype "bidirectional"))
      (node (ref "JP21") (pin "5") (pinfunction "5_5") (pintype "passive"))
      (node (ref "U3") (pin "10") (pinfunction "PD6(AIN0)_10") (pintype "bidirectional"))
    )
    (net (code "20") (name "/DI3") (class "Default")
      (node (ref "JP21") (pin "6") (pinfunction "6_6") (pintype "passive"))
      (node (ref "LED") (pin "3") (pinfunction "3_3") (pintype "bidirectional"))
      (node (ref "U3") (pin "11") (pinfunction "PD7(AIN1)_11") (pintype "bidirectional"))
    )
    (net (code "21") (name "/DI4") (class "Default")
      (node (ref "D4") (pin "3") (pinfunction "3_3") (pintype "bidirectional"))
      (node (ref "JP21") (pin "7") (pinfunction "7_7") (pintype "passive"))
      (node (ref "U3") (pin "12") (pinfunction "PB0(ICP)_12") (pintype "bidirectional"))
    )
    (net (code "22") (name "/DO1") (class "Default")
      (node (ref "D1") (pin "4") (pinfunction "4_4") (pintype "bidirectional"))
      (node (ref "JP21") (pin "8") (pinfunction "8_8") (pintype "passive"))
      (node (ref "U3") (pin "14") (pinfunction "PB2(SS/OC1B)_14") (pintype "bidirectional"))
    )
    (net (code "23") (name "/DO2") (class "Default")
      (node (ref "D2") (pin "4") (pinfunction "4_4") (pintype "bidirectional"))
      (node (ref "JP21") (pin "9") (pinfunction "9_9") (pintype "passive"))
      (node (ref "U3") (pin "15") (pinfunction "PB3(MOSI/OC2)_15") (pintype "bidirectional"))
    )
    (net (code "24") (name "/DO3") (class "Default")
      (node (ref "JP12") (pin "3") (pinfunction "3_3") (pintype "passive"))
      (node (ref "JP21") (pin "10") (pinfunction "10_10") (pintype "passive"))
      (node (ref "LED") (pin "4") (pinfunction "4_4") (pintype "bidirectional"))
      (node (ref "R13") (pin "2") (pinfunction "2_2") (pintype "passive"))
      (node (ref "U3") (pin "16") (pinfunction "PB4(MISO)_16") (pintype "bidirectional"))
    )
    (net (code "25") (name "/DO4") (class "Default")
      (node (ref "D4") (pin "4") (pinfunction "4_4") (pintype "bidirectional"))
      (node (ref "JP21") (pin "11") (pinfunction "11_11") (pintype "passive"))
      (node (ref "U3") (pin "17") (pinfunction "PB5(SCK)_17") (pintype "bidirectional"))
    )
    (net (code "26") (name "/DVCC") (class "Default")
      (node (ref "S2") (pin "2") (pinfunction "P_2") (pintype "passive"))
    )
    (net (code "27") (name "/ECG_IN+") (class "Default")
      (node (ref "IC2") (pin "2") (pinfunction "-_2") (pintype "input"))
      (node (ref "JP25") (pin "1") (pinfunction "1_1") (pintype "passive"))
    )
    (net (code "28") (name "/ECG_IN-") (class "Default")
      (node (ref "IC2") (pin "3") (pinfunction "+_3") (pintype "input"))
      (node (ref "JP25") (pin "3") (pinfunction "3_3") (pintype "passive"))
    )
    (net (code "29") (name "/EDA_IN+") (class "Default")
      (node (ref "IC6") (pin "2") (pinfunction "IN-_2") (pintype "input"))
      (node (ref "JP14") (pin "3") (pinfunction "3_3") (pintype "passive"))
      (node (ref "R23") (pin "1") (pinfunction "1_1") (pintype "passive"))
      (node (ref "R29") (pin "2") (pinfunction "2_2") (pintype "passive"))
    )
    (net (code "30") (name "/EDA_IN-") (class "Default")
      (node (ref "IC6") (pin "1") (pinfunction "OUT_1") (pintype "output"))
      (node (ref "JP14") (pin "1") (pinfunction "1_1") (pintype "passive"))
      (node (ref "R24") (pin "2") (pinfunction "2_2") (pintype "passive"))
      (node (ref "R29") (pin "1") (pinfunction "1_1") (pintype "passive"))
    )
    (net (code "31") (name "/EMG_A1_OUT") (class "Default")
      (node (ref "C31") (pin "2") (pinfunction "2_2") (pintype "passive"))
      (node (ref "IC5") (pin "8") (pinfunction "OUT_8") (pintype "output"))
      (node (ref "R35") (pin "1") (pinfunction "1_1") (pintype "passive"))
      (node (ref "R37") (pin "2") (pinfunction "2_2") (pintype "passive"))
    )
    (net (code "32") (name "/EMG_BUFF_OUT") (class "Default")
      (node (ref "IC5") (pin "6") (pinfunction "IN-_6") (pintype "input"))
      (node (ref "IC5") (pin "7") (pinfunction "OUT_7") (pintype "output"))
      (node (ref "R33") (pin "2") (pinfunction "2_2") (pintype "passive"))
    )
    (net (code "33") (name "/EMG_IN+") (class "Default")
      (node (ref "IC3") (pin "2") (pinfunction "-_2") (pintype "input"))
      (node (ref "JP13") (pin "1") (pinfunction "1_1") (pintype "passive"))
    )
    (net (code "34") (name "/EMG_IN-") (class "Default")
      (node (ref "IC3") (pin "3") (pinfunction "+_3") (pintype "input"))
      (node (ref "JP13") (pin "3") (pinfunction "3_3") (pintype "passive"))
    )
    (net (code "35") (name "/EMG_INA_OUT") (class "Default")
      (node (ref "IC3") (pin "6") (pinfunction "OUT_6") (pintype "output"))
      (node (ref "IC5") (pin "5") (pinfunction "IN+_5") (pintype "input"))
      (node (ref "R27") (pin "2") (pinfunction "2_2") (pintype "passive"))
    )
    (net (code "36") (name "/INA_ECG_OUT") (class "Default")
      (node (ref "IC2") (pin "6") (pinfunction "OUT_6") (pintype "output"))
      (node (ref "IC4") (pin "5") (pinfunction "IN+_5") (pintype "input"))
      (node (ref "R14") (pin "2") (pinfunction "2_2") (pintype "passive"))
    )
    (net (code "37") (name "/INA_ECG_VREF") (class "Default")
      (node (ref "C18") (pin "2") (pinfunction "2_2") (pintype "passive"))
      (node (ref "IC2") (pin "5") (pinfunction "REF_5") (pintype "passive"))
      (node (ref "IC4") (pin "1") (pinfunction "OUT_1") (pintype "output"))
    )
    (net (code "38") (name "/INA_EMG_VREF") (class "Default")
      (node (ref "C26") (pin "2") (pinfunction "2_2") (pintype "passive"))
      (node (ref "IC3") (pin "5") (pinfunction "REF_5") (pintype "passive"))
      (node (ref "IC5") (pin "1") (pinfunction "OUT_1") (pintype "output"))
    )
    (net (code "39") (name "/NC") (class "Default")
      (node (ref "JP18") (pin "6") (pinfunction "6_6") (pintype "passive"))
    )
    (net (code "40") (name "/RESET") (class "Default")
      (node (ref "JP16") (pin "6") (pinfunction "6_6") (pintype "passive"))
      (node (ref "R5") (pin "1") (pinfunction "1_1") (pintype "passive"))
      (node (ref "U3") (pin "29") (pinfunction "PC6(/RESET)_29") (pintype "bidirectional"))
    )
    (net (code "41") (name "/RXI") (class "Default")
      (node (ref "JP16") (pin "4") (pinfunction "4_4") (pintype "passive"))
      (node (ref "JP18") (pin "4") (pinfunction "4_4") (pintype "passive"))
      (node (ref "JP23") (pin "1") (pinfunction "1_1") (pintype "passive"))
      (node (ref "U3") (pin "30") (pinfunction "PD0(RXD)_30") (pintype "bidirectional"))
    )
    (net (code "42") (name "/SCL") (class "Default")
      (node (ref "JP20") (pin "3") (pinfunction "3_3") (pintype "passive"))
      (node (ref "R48") (pin "1") (pinfunction "1_1") (pintype "passive"))
      (node (ref "U3") (pin "28") (pinfunction "PC5(ADC5/SCL)_28") (pintype "bidirectional"))
    )
    (net (code "43") (name "/SDA") (class "Default")
      (node (ref "JP20") (pin "2") (pinfunction "2_2") (pintype "passive"))
      (node (ref "R45") (pin "1") (pinfunction "1_1") (pintype "passive"))
      (node (ref "U3") (pin "27") (pinfunction "PC4(ADC4/SDA)_27") (pintype "bidirectional"))
    )
    (net (code "44") (name "/ST") (class "Default")
      (node (ref "JP10") (pin "3") (pinfunction "3_3") (pintype "passive"))
      (node (ref "U4") (pin "2") (pinfunction "ST_2") (pintype "bidirectional"))
    )
    (net (code "45") (name "/STATUS_BT") (class "Default")
      (node (ref "JP16") (pin "2") (pinfunction "2_2") (pintype "passive"))
      (node (ref "JP18") (pin "2") (pinfunction "2_2") (pintype "passive"))
      (node (ref "U$1") (pin "P$24") (pinfunction "PIO(1)_P$24") (pintype "bidirectional"))
      (node (ref "U3") (pin "13") (pinfunction "PB1(OC1A)_13") (pintype "bidirectional"))
    )
    (net (code "46") (name "/TXO") (class "Default")
      (node (ref "JP16") (pin "5") (pinfunction "5_5") (pintype "passive"))
      (node (ref "JP18") (pin "5") (pinfunction "5_5") (pintype "passive"))
      (node (ref "JP24") (pin "1") (pinfunction "1_1") (pintype "passive"))
      (node (ref "U3") (pin "31") (pinfunction "PD1(TXD)_31") (pintype "bidirectional"))
    )
    (net (code "47") (name "/VBAT") (class "Default")
      (node (ref "C7") (pin "1") (pinfunction "1_1") (pintype "passive"))
      (node (ref "S2") (pin "3") (pinfunction "S_3") (pintype "passive"))
      (node (ref "U1") (pin "3") (pinfunction "VBAT_3") (pintype "input"))
    )
    (net (code "48") (name "/VDD") (class "Default")
      (node (ref "C35") (pin "1") (pinfunction "1_1") (pintype "passive"))
      (node (ref "C37") (pin "1") (pinfunction "1_1") (pintype "passive"))
      (node (ref "C40") (pin "1") (pinfunction "1_1") (pintype "passive"))
      (node (ref "JP17") (pin "3") (pinfunction "3_3") (pintype "passive"))
      (node (ref "JP18") (pin "3") (pinfunction "3_3") (pintype "passive"))
      (node (ref "JP20") (pin "11") (pinfunction "11_11") (pintype "passive"))
      (node (ref "JP4") (pin "2") (pinfunction "2_2") (pintype "passive"))
      (node (ref "JP7") (pin "3") (pinfunction "3_3") (pintype "passive"))
      (node (ref "L6") (pin "1") (pinfunction "1_1") (pintype "passive"))
      (node (ref "R43") (pin "2") (pinfunction "2_2") (pintype "passive"))
      (node (ref "U5") (pin "6") (pinfunction "OUT_6") (pintype "output"))
    )
    (net (code "49") (name "/VREF") (class "Default")
      (node (ref "ACC") (pin "4") (pinfunction "4_4") (pintype "bidirectional"))
      (node (ref "C21") (pin "1") (pinfunction "1_1") (pintype "passive"))
      (node (ref "C22") (pin "1") (pinfunction "1_1") (pintype "passive"))
      (node (ref "C30") (pin "1") (pinfunction "1_1") (pintype "passive"))
      (node (ref "C33") (pin "1") (pinfunction "1_1") (pintype "passive"))
      (node (ref "C34") (pin "1") (pinfunction "1_1") (pintype "passive"))
      (node (ref "ECG") (pin "4") (pinfunction "4_4") (pintype "bidirectional"))
      (node (ref "EDA") (pin "4") (pinfunction "4_4") (pintype "bidirectional"))
      (node (ref "EMG") (pin "4") (pinfunction "4_4") (pintype "bidirectional"))
      (node (ref "IC4") (pin "3") (pinfunction "IN+_3") (pintype "input"))
      (node (ref "IC5") (pin "3") (pinfunction "IN+_3") (pintype "input"))
      (node (ref "IC6") (pin "3") (pinfunction "IN+_3") (pintype "input"))
      (node (ref "JP19") (pin "2") (pinfunction "2_2") (pintype "passive"))
      (node (ref "JP21") (pin "2") (pinfunction "2_2") (pintype "passive"))
      (node (ref "JP22") (pin "2") (pinfunction "2_2") (pintype "passive"))
      (node (ref "JP6") (pin "3") (pinfunction "3_3") (pintype "passive"))
      (node (ref "JP8") (pin "3") (pinfunction "3_3") (pintype "passive"))
      (node (ref "JP9") (pin "3") (pinfunction "3_3") (pintype "passive"))
      (node (ref "R18") (pin "2") (pinfunction "2_2") (pintype "passive"))
      (node (ref "R22") (pin "2") (pinfunction "2_2") (pintype "passive"))
      (node (ref "R30") (pin "1") (pinfunction "1_1") (pintype "passive"))
      (node (ref "R31") (pin "1") (pinfunction "1_1") (pintype "passive"))
      (node (ref "R36") (pin "2") (pinfunction "2_2") (pintype "passive"))
      (node (ref "R40") (pin "2") (pinfunction "2_2") (pintype "passive"))
      (node (ref "R46") (pin "1") (pinfunction "1_1") (pintype "passive"))
    )
    (net (code "50") (name "/X_OUT") (class "Default")
      (node (ref "C14") (pin "2") (pinfunction "2_2") (pintype "passive"))
      (node (ref "JP5") (pin "1") (pinfunction "1_1") (pintype "passive"))
      (node (ref "U4") (pin "12") (pinfunction "XOUT_12") (pintype "bidirectional"))
    )
    (net (code "51") (name "/Y_OUT") (class "Default")
      (node (ref "C15") (pin "1") (pinfunction "1_1") (pintype "passive"))
      (node (ref "JP5") (pin "2") (pinfunction "2_2") (pintype "passive"))
      (node (ref "U4") (pin "10") (pinfunction "YOUT_10") (pintype "bidirectional"))
    )
    (net (code "52") (name "GND") (class "Default")
      (node (ref "ACC") (pin "2") (pinfunction "2_2") (pintype "bidirectional"))
      (node (ref "C10") (pin "2") (pinfunction "2_2") (pintype "passive"))
      (node (ref "C11") (pin "2") (pinfunction "2_2") (pintype "passive"))
      (node (ref "C12") (pin "2") (pinfunction "2_2") (pintype "passive"))
      (node (ref "C13") (pin "2") (pinfunction "2_2") (pintype "passive"))
      (node (ref "C14") (pin "1") (pinfunction "1_1") (pintype "passive"))
      (node (ref "C15") (pin "2") (pinfunction "2_2") (pintype "passive"))
      (node (ref "C16") (pin "2") (pinfunction "2_2") (pintype "passive"))
      (node (ref "C17") (pin "2") (pinfunction "2_2") (pintype "passive"))
      (node (ref "C19") (pin "2") (pinfunction "2_2") (pintype "passive"))
      (node (ref "C2") (pin "2") (pinfunction "2_2") (pintype "passive"))
      (node (ref "C24") (pin "2") (pinfunction "2_2") (pintype "passive"))
      (node (ref "C25") (pin "2") (pinfunction "2_2") (pintype "passive"))
      (node (ref "C27") (pin "2") (pinfunction "2_2") (pintype "passive"))
      (node (ref "C29") (pin "2") (pinfunction "2_2") (pintype "passive"))
      (node (ref "C3") (pin "2") (pinfunction "2_2") (pintype "passive"))
      (node (ref "C30") (pin "2") (pinfunction "2_2") (pintype "passive"))
      (node (ref "C39") (pin "2") (pinfunction "2_2") (pintype "passive"))
      (node (ref "C4") (pin "2") (pinfunction "2_2") (pintype "passive"))
      (node (ref "C41") (pin "2") (pinfunction "2_2") (pintype "passive"))
      (node (ref "C5") (pin "2") (pinfunction "2_2") (pintype "passive"))
      (node (ref "C9") (pin "2") (pinfunction "2_2") (pintype "passive"))
      (node (ref "D1") (pin "2") (pinfunction "2_2") (pintype "bidirectional"))
      (node (ref "D2") (pin "2") (pinfunction "2_2") (pintype "bidirectional"))
      (node (ref "D4") (pin "2") (pinfunction "2_2") (pintype "bidirectional"))
      (node (ref "ECG") (pin "2") (pinfunction "2_2") (pintype "bidirectional"))
      (node (ref "EDA") (pin "2") (pinfunction "2_2") (pintype "bidirectional"))
      (node (ref "EMG") (pin "2") (pinfunction "2_2") (pintype "bidirectional"))
      (node (ref "IC1") (pin "2") (pinfunction "-VS_2") (pintype "input"))
      (node (ref "IC2") (pin "4") (pinfunction "-V_4") (pintype "power_in"))
      (node (ref "IC3") (pin "4") (pinfunction "-V_4") (pintype "power_in"))
      (node (ref "IC4") (pin "11") (pinfunction "V-_11") (pintype "power_in"))
      (node (ref "IC5") (pin "11") (pinfunction "V-_11") (pintype "power_in"))
      (node (ref "IC6") (pin "4") (pinfunction "V-_4") (pintype "power_in"))
      (node (ref "JP10") (pin "2") (pinfunction "2_2") (pintype "passive"))
      (node (ref "JP12") (pin "2") (pinfunction "2_2") (pintype "passive"))
      (node (ref "JP19") (pin "1") (pinfunction "1_1") (pintype "passive"))
      (node (ref "JP21") (pin "3") (pinfunction "3_3") (pintype "passive"))
      (node (ref "JP22") (pin "1") (pinfunction "1_1") (pintype "passive"))
      (node (ref "JP26") (pin "2") (pinfunction "2_2") (pintype "passive"))
      (node (ref "JP6") (pin "2") (pinfunction "2_2") (pintype "passive"))
      (node (ref "JP8") (pin "2") (pinfunction "2_2") (pintype "passive"))
      (node (ref "JP9") (pin "2") (pinfunction "2_2") (pintype "passive"))
      (node (ref "LED") (pin "2") (pinfunction "2_2") (pintype "bidirectional"))
      (node (ref "LED4") (pin "C") (pinfunction "C_C") (pintype "passive"))
      (node (ref "R1") (pin "1") (pinfunction "1_1") (pintype "passive"))
      (node (ref "R10") (pin "1") (pinfunction "1_1") (pintype "passive"))
      (node (ref "R12") (pin "1") (pinfunction "1_1") (pintype "passive"))
      (node (ref "R26") (pin "2") (pinfunction "2_2") (pintype "passive"))
      (node (ref "R4") (pin "1") (pinfunction "1_1") (pintype "passive"))
      (node (ref "R41") (pin "1") (pinfunction "1_1") (pintype "passive"))
      (node (ref "R42") (pin "1") (pinfunction "1_1") (pintype "passive"))
      (node (ref "R44") (pin "1") (pinfunction "1_1") (pintype "passive"))
      (node (ref "R6") (pin "1") (pinfunction "1_1") (pintype "passive"))
      (node (ref "R7") (pin "1") (pinfunction "1_1") (pintype "passive"))
      (node (ref "R8") (pin "1") (pinfunction "1_1") (pintype "passive"))
      (node (ref "R9") (pin "1") (pinfunction "1_1") (pintype "passive"))
      (node (ref "U$2") (pin "2") (pinfunction "AGND_2") (pintype "bidirectional"))
      (node (ref "U3") (pin "21") (pinfunction "GND_21") (pintype "bidirectional"))
      (node (ref "U3") (pin "3") (pinfunction "GND_3") (pintype "bidirectional"))
      (node (ref "U3") (pin "5") (pinfunction "AGND_5") (pintype "bidirectional"))
      (node (ref "U4") (pin "3") (pinfunction "COM_3") (pintype "bidirectional"))
      (node (ref "U4") (pin "5") (pinfunction "COM_5") (pintype "bidirectional"))
      (node (ref "U4") (pin "6") (pinfunction "COM_6") (pintype "bidirectional"))
      (node (ref "U4") (pin "7") (pinfunction "COM_7") (pintype "bidirectional"))
    )
    (net (code "53") (name "Net-(C20-Pad1)") (class "Default")
      (node (ref "C20") (pin "1") (pinfunction "1_1") (pintype "passive"))
      (node (ref "R15") (pin "1") (pinfunction "1_1") (pintype "passive"))
      (node (ref "R16") (pin "2") (pinfunction "2_2") (pintype "passive"))
    )
    (net (code "54") (name "Net-(C23-Pad1)") (class "Default")
      (node (ref "C23") (pin "1") (pinfunction "1_1") (pintype "passive"))
      (node (ref "R19") (pin "1") (pinfunction "1_1") (pintype "passive"))
      (node (ref "R20") (pin "2") (pinfunction "2_2") (pintype "passive"))
    )
    (net (code "55") (name "Net-(C28-Pad1)") (class "Default")
      (node (ref "C28") (pin "1") (pinfunction "1_1") (pintype "passive"))
      (node (ref "R24") (pin "1") (pinfunction "1_1") (pintype "passive"))
      (node (ref "R32") (pin "2") (pinfunction "2_2") (pintype "passive"))
    )
    (net (code "56") (name "Net-(C31-Pad1)") (class "Default")
      (node (ref "C31") (pin "1") (pinfunction "1_1") (pintype "passive"))
      (node (ref "R33") (pin "1") (pinfunction "1_1") (pintype "passive"))
      (node (ref "R34") (pin "2") (pinfunction "2_2") (pintype "passive"))
    )
    (net (code "57") (name "Net-(C32-Pad1)") (class "Default")
      (node (ref "C32") (pin "1") (pinfunction "1_1") (pintype "passive"))
      (node (ref "R37") (pin "1") (pinfunction "1_1") (pintype "passive"))
      (node (ref "R38") (pin "2") (pinfunction "2_2") (pintype "passive"))
    )
    (net (code "58") (name "Net-(IC1-+VS)") (class "Default")
      (node (ref "C2") (pin "1") (pinfunction "1_1") (pintype "passive"))
      (node (ref "IC1") (pin "5") (pinfunction "+VS_5") (pintype "input"))
      (node (ref "L1") (pin "2") (pinfunction "2_2") (pintype "passive"))
    )
    (net (code "59") (name "Net-(IC1-IN+)") (class "Default")
      (node (ref "C39") (pin "1") (pinfunction "1_1") (pintype "passive"))
      (node (ref "IC1") (pin "3") (pinfunction "IN+_3") (pintype "input"))
      (node (ref "R3") (pin "1") (pinfunction "1_1") (pintype "passive"))
      (node (ref "R4") (pin "2") (pinfunction "2_2") (pintype "passive"))
    )
    (net (code "60") (name "Net-(IC1-IN-)") (class "Default")
      (node (ref "IC1") (pin "1") (pinfunction "OUT_1") (pintype "output"))
      (node (ref "IC1") (pin "4") (pinfunction "IN-_4") (pintype "input"))
      (node (ref "R46") (pin "2") (pinfunction "2_2") (pintype "passive"))
    )
    (net (code "61") (name "Net-(IC2-+V)") (class "Default")
      (node (ref "C17") (pin "1") (pinfunction "1_1") (pintype "passive"))
      (node (ref "IC2") (pin "7") (pinfunction "+V_7") (pintype "power_in"))
      (node (ref "L11") (pin "1") (pinfunction "1_1") (pintype "passive"))
    )
    (net (code "62") (name "Net-(IC2-RG-Pad1)") (class "Default")
      (node (ref "IC2") (pin "1") (pinfunction "RG_1") (pintype "passive"))
      (node (ref "RG") (pin "2") (pinfunction "2_2") (pintype "passive"))
    )
    (net (code "63") (name "Net-(IC2-RG-Pad8)") (class "Default")
      (node (ref "IC2") (pin "8") (pinfunction "RG_8") (pintype "passive"))
      (node (ref "RG") (pin "1") (pinfunction "1_1") (pintype "passive"))
    )
    (net (code "64") (name "Net-(IC3-+V)") (class "Default")
      (node (ref "C29") (pin "1") (pinfunction "1_1") (pintype "passive"))
      (node (ref "IC3") (pin "7") (pinfunction "+V_7") (pintype "power_in"))
      (node (ref "L14") (pin "2") (pinfunction "2_2") (pintype "passive"))
    )
    (net (code "65") (name "Net-(IC3-RG-Pad1)") (class "Default")
      (node (ref "IC3") (pin "1") (pinfunction "RG_1") (pintype "passive"))
      (node (ref "R28") (pin "1") (pinfunction "1_1") (pintype "passive"))
    )
    (net (code "66") (name "Net-(IC3-RG-Pad8)") (class "Default")
      (node (ref "IC3") (pin "8") (pinfunction "RG_8") (pintype "passive"))
      (node (ref "R28") (pin "2") (pinfunction "2_2") (pintype "passive"))
    )
    (net (code "67") (name "Net-(IC4A-IN-)") (class "Default")
      (node (ref "C18") (pin "1") (pinfunction "1_1") (pintype "passive"))
      (node (ref "IC4") (pin "2") (pinfunction "IN-_2") (pintype "input"))
      (node (ref "R14") (pin "1") (pinfunction "1_1") (pintype "passive"))
    )
    (net (code "68") (name "Net-(IC4C-IN+)") (class "Default")
      (node (ref "C21") (pin "2") (pinfunction "2_2") (pintype "passive"))
      (node (ref "IC4") (pin "10") (pinfunction "IN+_10") (pintype "input"))
      (node (ref "R16") (pin "1") (pinfunction "1_1") (pintype "passive"))
    )
    (net (code "69") (name "Net-(IC4C-IN-)") (class "Default")
      (node (ref "IC4") (pin "9") (pinfunction "IN-_9") (pintype "input"))
      (node (ref "R17") (pin "2") (pinfunction "2_2") (pintype "passive"))
      (node (ref "R18") (pin "1") (pinfunction "1_1") (pintype "passive"))
    )
    (net (code "70") (name "Net-(IC4D-IN+)") (class "Default")
      (node (ref "C22") (pin "2") (pinfunction "2_2") (pintype "passive"))
      (node (ref "IC4") (pin "12") (pinfunction "IN+_12") (pintype "input"))
      (node (ref "R20") (pin "1") (pinfunction "1_1") (pintype "passive"))
    )
    (net (code "71") (name "Net-(IC4D-IN-)") (class "Default")
      (node (ref "IC4") (pin "13") (pinfunction "IN-_13") (pintype "input"))
      (node (ref "R21") (pin "2") (pinfunction "2_2") (pintype "passive"))
      (node (ref "R22") (pin "1") (pinfunction "1_1") (pintype "passive"))
    )
    (net (code "72") (name "Net-(IC4E-V+)") (class "Default")
      (node (ref "C19") (pin "1") (pinfunction "1_1") (pintype "passive"))
      (node (ref "IC4") (pin "4") (pinfunction "V+_4") (pintype "power_in"))
      (node (ref "L12") (pin "1") (pinfunction "1_1") (pintype "passive"))
    )
    (net (code "73") (name "Net-(IC5A-IN-)") (class "Default")
      (node (ref "C26") (pin "1") (pinfunction "1_1") (pintype "passive"))
      (node (ref "IC5") (pin "2") (pinfunction "IN-_2") (pintype "input"))
      (node (ref "R27") (pin "1") (pinfunction "1_1") (pintype "passive"))
    )
    (net (code "74") (name "Net-(IC5C-IN+)") (class "Default")
      (node (ref "C33") (pin "2") (pinfunction "2_2") (pintype "passive"))
      (node (ref "IC5") (pin "10") (pinfunction "IN+_10") (pintype "input"))
      (node (ref "R34") (pin "1") (pinfunction "1_1") (pintype "passive"))
    )
    (net (code "75") (name "Net-(IC5C-IN-)") (class "Default")
      (node (ref "IC5") (pin "9") (pinfunction "IN-_9") (pintype "input"))
      (node (ref "R35") (pin "2") (pinfunction "2_2") (pintype "passive"))
      (node (ref "R36") (pin "1") (pinfunction "1_1") (pintype "passive"))
    )
    (net (code "76") (name "Net-(IC5D-IN+)") (class "Default")
      (node (ref "C34") (pin "2") (pinfunction "2_2") (pintype "passive"))
      (node (ref "IC5") (pin "12") (pinfunction "IN+_12") (pintype "input"))
      (node (ref "R38") (pin "1") (pinfunction "1_1") (pintype "passive"))
    )
    (net (code "77") (name "Net-(IC5D-IN-)") (class "Default")
      (node (ref "IC5") (pin "13") (pinfunction "IN-_13") (pintype "input"))
      (node (ref "R39") (pin "2") (pinfunction "2_2") (pintype "passive"))
      (node (ref "R40") (pin "1") (pinfunction "1_1") (pintype "passive"))
    )
    (net (code "78") (name "Net-(IC5E-V+)") (class "Default")
      (node (ref "C27") (pin "1") (pinfunction "1_1") (pintype "passive"))
      (node (ref "IC5") (pin "4") (pinfunction "V+_4") (pintype "power_in"))
      (node (ref "L15") (pin "2") (pinfunction "2_2") (pintype "passive"))
    )
    (net (code "79") (name "Net-(IC6B-IN+)") (class "Default")
      (node (ref "C25") (pin "1") (pinfunction "1_1") (pintype "passive"))
      (node (ref "IC6") (pin "5") (pinfunction "IN+_5") (pintype "input"))
      (node (ref "R32") (pin "1") (pinfunction "1_1") (pintype "passive"))
    )
    (net (code "80") (name "Net-(IC6B-IN-)") (class "Default")
      (node (ref "IC6") (pin "6") (pinfunction "IN-_6") (pintype "input"))
      (node (ref "R25") (pin "2") (pinfunction "2_2") (pintype "passive"))
      (node (ref "R26") (pin "1") (pinfunction "1_1") (pintype "passive"))
    )
    (net (code "81") (name "Net-(IC6C-V+)") (class "Default")
      (node (ref "C24") (pin "1") (pinfunction "1_1") (pintype "passive"))
      (node (ref "IC6") (pin "8") (pinfunction "V+_8") (pintype "power_in"))
      (node (ref "L13") (pin "1") (pinfunction "1_1") (pintype "passive"))
    )
    (net (code "82") (name "Net-(JP2-VCC)") (class "Default")
      (node (ref "JP2") (pin "1") (pinfunction "VCC_1") (pintype "bidirectional"))
      (node (ref "PTC") (pin "1") (pinfunction "1_1") (pintype "passive"))
    )
    (net (code "83") (name "Net-(JP13-Pad2)") (class "Default")
      (node (ref "JP13") (pin "2") (pinfunction "2_2") (pintype "passive"))
      (node (ref "R31") (pin "2") (pinfunction "2_2") (pintype "passive"))
    )
    (net (code "84") (name "Net-(JP16-Pad3)") (class "Default")
      (node (ref "JP16") (pin "3") (pinfunction "3_3") (pintype "passive"))
      (node (ref "JP3") (pin "1") (pinfunction "1_1") (pintype "passive"))
      (node (ref "JP4") (pin "1") (pinfunction "1_1") (pintype "passive"))
    )
    (net (code "85") (name "Net-(JP25-Pad2)") (class "Default")
      (node (ref "JP25") (pin "2") (pinfunction "2_2") (pintype "passive"))
      (node (ref "R30") (pin "2") (pinfunction "2_2") (pintype "passive"))
    )
    (net (code "86") (name "Net-(LED1-PadA)") (class "Default")
      (node (ref "LED1") (pin "A") (pinfunction "A_A") (pintype "passive"))
      (node (ref "R2") (pin "2") (pinfunction "2_2") (pintype "passive"))
    )
    (net (code "87") (name "Net-(LED2-PadC)") (class "Default")
      (node (ref "LED2") (pin "C") (pinfunction "C_C") (pintype "passive"))
      (node (ref "R6") (pin "2") (pinfunction "2_2") (pintype "passive"))
    )
    (net (code "88") (name "Net-(LED3-PadC)") (class "Default")
      (node (ref "LED3") (pin "C") (pinfunction "C_C") (pintype "passive"))
      (node (ref "R7") (pin "2") (pinfunction "2_2") (pintype "passive"))
    )
    (net (code "89") (name "Net-(LED4-PadA)") (class "Default")
      (node (ref "LED4") (pin "A") (pinfunction "A_A") (pintype "passive"))
      (node (ref "R13") (pin "1") (pinfunction "1_1") (pintype "passive"))
    )
    (net (code "90") (name "Net-(Q1-2)") (class "Default")
      (node (ref "C11") (pin "1") (pinfunction "1_1") (pintype "passive"))
      (node (ref "Q1") (pin "3") (pinfunction "2_3") (pintype "passive"))
      (node (ref "U3") (pin "8") (pinfunction "PB7(XTAL2/TOSC2)_8") (pintype "bidirectional"))
    )
    (net (code "91") (name "Net-(U$1-3.3V)") (class "Default")
      (node (ref "C42") (pin "1") (pinfunction "1_1") (pintype "passive"))
      (node (ref "L6") (pin "2") (pinfunction "2_2") (pintype "passive"))
      (node (ref "U$1") (pin "P$12") (pinfunction "3.3V_P$12") (pintype "bidirectional"))
    )
    (net (code "92") (name "Net-(U$1-UART-RX)") (class "Default")
      (node (ref "JP24") (pin "2") (pinfunction "2_2") (pintype "passive"))
      (node (ref "U$1") (pin "P$2") (pinfunction "UART-RX_P$2") (pintype "bidirectional"))
    )
    (net (code "93") (name "Net-(U$1-UART-TX)") (class "Default")
      (node (ref "JP23") (pin "2") (pinfunction "2_2") (pintype "passive"))
      (node (ref "U$1") (pin "P$1") (pinfunction "UART-TX_P$1") (pintype "bidirectional"))
    )
    (net (code "94") (name "Net-(U1-PROG)") (class "Default")
      (node (ref "R1") (pin "2") (pinfunction "2_2") (pintype "passive"))
      (node (ref "U1") (pin "5") (pinfunction "PROG_5") (pintype "input"))
    )
    (net (code "95") (name "Net-(U1-STAT)") (class "Default")
      (node (ref "LED1") (pin "C") (pinfunction "C_C") (pintype "passive"))
      (node (ref "U1") (pin "1") (pinfunction "STAT_1") (pintype "input"))
    )
    (net (code "96") (name "Net-(U1-VDD)") (class "Default")
      (node (ref "C6") (pin "1") (pinfunction "1_1") (pintype "passive"))
      (node (ref "PTC") (pin "2") (pinfunction "2_2") (pintype "passive"))
      (node (ref "R2") (pin "1") (pinfunction "1_1") (pintype "passive"))
      (node (ref "U1") (pin "4") (pinfunction "VDD_4") (pintype "power_in"))
    )
    (net (code "97") (name "Net-(U2-FB)") (class "Default")
      (node (ref "C5") (pin "1") (pinfunction "1_1") (pintype "passive"))
      (node (ref "U2") (pin "4") (pinfunction "FB_4") (pintype "output"))
    )
    (net (code "98") (name "Net-(U2-SW)") (class "Default")
      (node (ref "L10") (pin "1") (pinfunction "1_1") (pintype "passive"))
      (node (ref "U2") (pin "5") (pinfunction "SW_5") (pintype "output"))
    )
    (net (code "99") (name "Net-(U3-AREF)") (class "Default")
      (node (ref "C10") (pin "1") (pinfunction "1_1") (pintype "passive"))
      (node (ref "U3") (pin "20") (pinfunction "AREF_20") (pintype "bidirectional"))
    )
    (net (code "100") (name "Net-(U3-AVCC)") (class "Default")
      (node (ref "C4") (pin "1") (pinfunction "1_1") (pintype "passive"))
      (node (ref "L9") (pin "2") (pinfunction "2_2") (pintype "passive"))
      (node (ref "U3") (pin "18") (pinfunction "AVCC_18") (pintype "bidirectional"))
    )
    (net (code "101") (name "Net-(U3-PB6(XTAL1{slash}TOSC1))") (class "Default")
      (node (ref "C12") (pin "1") (pinfunction "1_1") (pintype "passive"))
      (node (ref "Q1") (pin "1") (pinfunction "1_1") (pintype "passive"))
      (node (ref "U3") (pin "7") (pinfunction "PB6(XTAL1/TOSC1)_7") (pintype "bidirectional"))
    )
    (net (code "102") (name "Net-(U5-FB)") (class "Default")
      (node (ref "C37") (pin "2") (pinfunction "2_2") (pintype "passive"))
      (node (ref "R43") (pin "1") (pinfunction "1_1") (pintype "passive"))
      (node (ref "R47") (pin "2") (pinfunction "2_2") (pintype "passive"))
      (node (ref "U5") (pin "5") (pinfunction "FB_5") (pintype "input"))
    )
    (net (code "103") (name "Net-(U5-NR)") (class "Default")
      (node (ref "C38") (pin "1") (pinfunction "1_1") (pintype "passive"))
      (node (ref "U5") (pin "4") (pinfunction "NR_4") (pintype "input"))
    )
    (net (code "104") (name "VCC") (class "Default")
      (node (ref "ACC") (pin "1") (pinfunction "1_1") (pintype "bidirectional"))
      (node (ref "C13") (pin "1") (pinfunction "1_1") (pintype "passive"))
      (node (ref "C3") (pin "1") (pinfunction "1_1") (pintype "passive"))
      (node (ref "C41") (pin "1") (pinfunction "1_1") (pintype "passive"))
      (node (ref "C9") (pin "1") (pinfunction "1_1") (pintype "passive"))
      (node (ref "D1") (pin "1") (pinfunction "1_1") (pintype "bidirectional"))
      (node (ref "D2") (pin "1") (pinfunction "1_1") (pintype "bidirectional"))
      (node (ref "D4") (pin "1") (pinfunction "1_1") (pintype "bidirectional"))
      (node (ref "ECG") (pin "1") (pinfunction "1_1") (pintype "bidirectional"))
      (node (ref "EDA") (pin "1") (pinfunction "1_1") (pintype "bidirectional"))
      (node (ref "EMG") (pin "1") (pinfunction "1_1") (pintype "bidirectional"))
      (node (ref "JP10") (pin "1") (pinfunction "1_1") (pintype "passive"))
      (node (ref "JP12") (pin "1") (pinfunction "1_1") (pintype "passive"))
      (node (ref "JP19") (pin "3") (pinfunction "3_3") (pintype "passive"))
      (node (ref "JP21") (pin "1") (pinfunction "1_1") (pintype "passive"))
      (node (ref "JP22") (pin "3") (pinfunction "3_3") (pintype "passive"))
      (node (ref "JP26") (pin "1") (pinfunction "1_1") (pintype "passive"))
      (node (ref "JP3") (pin "2") (pinfunction "2_2") (pintype "passive"))
      (node (ref "JP6") (pin "1") (pinfunction "1_1") (pintype "passive"))
      (node (ref "JP8") (pin "1") (pinfunction "1_1") (pintype "passive"))
      (node (ref "JP9") (pin "1") (pinfunction "1_1") (pintype "passive"))
      (node (ref "L1") (pin "1") (pinfunction "1_1") (pintype "passive"))
      (node (ref "L10") (pin "2") (pinfunction "2_2") (pintype "passive"))
      (node (ref "L11") (pin "2") (pinfunction "2_2") (pintype "passive"))
      (node (ref "L12") (pin "2") (pinfunction "2_2") (pintype "passive"))
      (node (ref "L13") (pin "2") (pinfunction "2_2") (pintype "passive"))
      (node (ref "L14") (pin "1") (pinfunction "1_1") (pintype "passive"))
      (node (ref "L15") (pin "1") (pinfunction "1_1") (pintype "passive"))
      (node (ref "L9") (pin "1") (pinfunction "1_1") (pintype "passive"))
      (node (ref "LED") (pin "1") (pinfunction "1_1") (pintype "bidirectional"))
      (node (ref "R23") (pin "2") (pinfunction "2_2") (pintype "passive"))
      (node (ref "R3") (pin "2") (pinfunction "2_2") (pintype "passive"))
      (node (ref "R45") (pin "2") (pinfunction "2_2") (pintype "passive"))
      (node (ref "R48") (pin "2") (pinfunction "2_2") (pintype "passive"))
      (node (ref "R5") (pin "2") (pinfunction "2_2") (pintype "passive"))
      (node (ref "U$10") (pin "COLLECTOR") (pinfunction "C1_COLLECTOR") (pintype "passive"))
      (node (ref "U3") (pin "4") (pinfunction "VCC_4") (pintype "bidirectional"))
      (node (ref "U3") (pin "6") (pinfunction "VCC_6") (pintype "bidirectional"))
      (node (ref "U4") (pin "14") (pinfunction "VS_14") (pintype "bidirectional"))
      (node (ref "U4") (pin "15") (pinfunction "VS_15") (pintype "bidirectional"))
    )
    (net (code "105") (name "unconnected-(JP2-D+-Pad3)") (class "Default")
      (node (ref "JP2") (pin "3") (pinfunction "D+_3") (pintype "bidirectional"))
    )
    (net (code "106") (name "unconnected-(JP2-D--Pad2)") (class "Default")
      (node (ref "JP2") (pin "2") (pinfunction "D-_2") (pintype "bidirectional"))
    )
    (net (code "107") (name "unconnected-(JP2-ID-Pad4)") (class "Default")
      (node (ref "JP2") (pin "4") (pinfunction "ID_4") (pintype "bidirectional"))
    )
    (net (code "108") (name "unconnected-(JP12-Pad4)") (class "Default")
      (node (ref "JP12") (pin "4") (pinfunction "4_4") (pintype "passive"))
    )
    (net (code "109") (name "unconnected-(JP14-Pad2)") (class "Default")
      (node (ref "JP14") (pin "2") (pinfunction "2_2") (pintype "passive"))
    )
    (net (code "110") (name "unconnected-(JP26-Pad3)") (class "Default")
      (node (ref "JP26") (pin "3") (pinfunction "3_3") (pintype "passive"))
    )
    (net (code "111") (name "unconnected-(JP27-Pad1)") (class "Default")
      (node (ref "JP27") (pin "1") (pinfunction "1_1") (pintype "passive"))
    )
    (net (code "112") (name "unconnected-(JP28-Pad1)") (class "Default")
      (node (ref "JP28") (pin "1") (pinfunction "1_1") (pintype "passive"))
    )
    (net (code "113") (name "unconnected-(S1-S-Pad3)") (class "Default")
      (node (ref "S1") (pin "3") (pinfunction "S_3") (pintype "passive"))
    )
    (net (code "114") (name "unconnected-(U$1-AIO(0)-PadP$9)") (class "Default")
      (node (ref "U$1") (pin "P$9") (pinfunction "AIO(0)_P$9") (pintype "bidirectional"))
    )
    (net (code "115") (name "unconnected-(U$1-AIO(1)-PadP$10)") (class "Default")
      (node (ref "U$1") (pin "P$10") (pinfunction "AIO(1)_P$10") (pintype "bidirectional"))
    )
    (net (code "116") (name "unconnected-(U$1-PCM-CLK-PadP$5)") (class "Default")
      (node (ref "U$1") (pin "P$5") (pinfunction "PCM-CLK_P$5") (pintype "bidirectional"))
    )
    (net (code "117") (name "unconnected-(U$1-PCM-IN-PadP$7)") (class "Default")
      (node (ref "U$1") (pin "P$7") (pinfunction "PCM-IN_P$7") (pintype "bidirectional"))
    )
    (net (code "118") (name "unconnected-(U$1-PCM-OUT-PadP$6)") (class "Default")
      (node (ref "U$1") (pin "P$6") (pinfunction "PCM-OUT_P$6") (pintype "bidirectional"))
    )
    (net (code "119") (name "unconnected-(U$1-PCM-SYNC-PadP$8)") (class "Default")
      (node (ref "U$1") (pin "P$8") (pinfunction "PCM-SYNC_P$8") (pintype "bidirectional"))
    )
    (net (code "120") (name "unconnected-(U$1-PIO(0)-PadP$23)") (class "Default")
      (node (ref "U$1") (pin "P$23") (pinfunction "PIO(0)_P$23") (pintype "bidirectional"))
    )
    (net (code "121") (name "unconnected-(U$1-PIO(2)-PadP$25)") (class "Default")
      (node (ref "U$1") (pin "P$25") (pinfunction "PIO(2)_P$25") (pintype "bidirectional"))
    )
    (net (code "122") (name "unconnected-(U$1-PIO(3)-PadP$26)") (class "Default")
      (node (ref "U$1") (pin "P$26") (pinfunction "PIO(3)_P$26") (pintype "bidirectional"))
    )
    (net (code "123") (name "unconnected-(U$1-PIO(4)-PadP$27)") (class "Default")
      (node (ref "U$1") (pin "P$27") (pinfunction "PIO(4)_P$27") (pintype "bidirectional"))
    )
    (net (code "124") (name "unconnected-(U$1-PIO(5)-PadP$28)") (class "Default")
      (node (ref "U$1") (pin "P$28") (pinfunction "PIO(5)_P$28") (pintype "bidirectional"))
    )
    (net (code "125") (name "unconnected-(U$1-PIO(6)-PadP$29)") (class "Default")
      (node (ref "U$1") (pin "P$29") (pinfunction "PIO(6)_P$29") (pintype "bidirectional"))
    )
    (net (code "126") (name "unconnected-(U$1-PIO(7)-PadP$30)") (class "Default")
      (node (ref "U$1") (pin "P$30") (pinfunction "PIO(7)_P$30") (pintype "bidirectional"))
    )
    (net (code "127") (name "unconnected-(U$1-PIO(8)-PadP$31)") (class "Default")
      (node (ref "U$1") (pin "P$31") (pinfunction "PIO(8)_P$31") (pintype "bidirectional"))
    )
    (net (code "128") (name "unconnected-(U$1-PIO(9)-PadP$32)") (class "Default")
      (node (ref "U$1") (pin "P$32") (pinfunction "PIO(9)_P$32") (pintype "bidirectional"))
    )
    (net (code "129") (name "unconnected-(U$1-PIO(10)-PadP$33)") (class "Default")
      (node (ref "U$1") (pin "P$33") (pinfunction "PIO(10)_P$33") (pintype "bidirectional"))
    )
    (net (code "130") (name "unconnected-(U$1-PIO(11)-PadP$34)") (class "Default")
      (node (ref "U$1") (pin "P$34") (pinfunction "PIO(11)_P$34") (pintype "bidirectional"))
    )
    (net (code "131") (name "unconnected-(U$1-RESET-PadP$11)") (class "Default")
      (node (ref "U$1") (pin "P$11") (pinfunction "RESET_P$11") (pintype "bidirectional"))
    )
    (net (code "132") (name "unconnected-(U$1-SPI-CLK-PadP$19)") (class "Default")
      (node (ref "U$1") (pin "P$19") (pinfunction "SPI-CLK_P$19") (pintype "bidirectional"))
    )
    (net (code "133") (name "unconnected-(U$1-SPI-CSB-PadP$16)") (class "Default")
      (node (ref "U$1") (pin "P$16") (pinfunction "SPI-CSB_P$16") (pintype "bidirectional"))
    )
    (net (code "134") (name "unconnected-(U$1-SPI-MISO-PadP$18)") (class "Default")
      (node (ref "U$1") (pin "P$18") (pinfunction "SPI-MISO_P$18") (pintype "bidirectional"))
    )
    (net (code "135") (name "unconnected-(U$1-SPI-MOSI-PadP$17)") (class "Default")
      (node (ref "U$1") (pin "P$17") (pinfunction "SPI-MOSI_P$17") (pintype "bidirectional"))
    )
    (net (code "136") (name "unconnected-(U$1-UART-CTS-PadP$3)") (class "Default")
      (node (ref "U$1") (pin "P$3") (pinfunction "UART-CTS_P$3") (pintype "bidirectional"))
    )
    (net (code "137") (name "unconnected-(U$1-UART-RTS-PadP$4)") (class "Default")
      (node (ref "U$1") (pin "P$4") (pinfunction "UART-RTS_P$4") (pintype "bidirectional"))
    )
    (net (code "138") (name "unconnected-(U$1-USB-D+-PadP$20)") (class "Default")
      (node (ref "U$1") (pin "P$20") (pinfunction "USB-D+_P$20") (pintype "bidirectional"))
    )
    (net (code "139") (name "unconnected-(U$1-USB-D--PadP$15)") (class "Default")
      (node (ref "U$1") (pin "P$15") (pinfunction "USB-D-_P$15") (pintype "bidirectional"))
    )
  )
)
